# LEDpanelmpsl.net
KiCad netlist of a schematic drawn in EAGLE
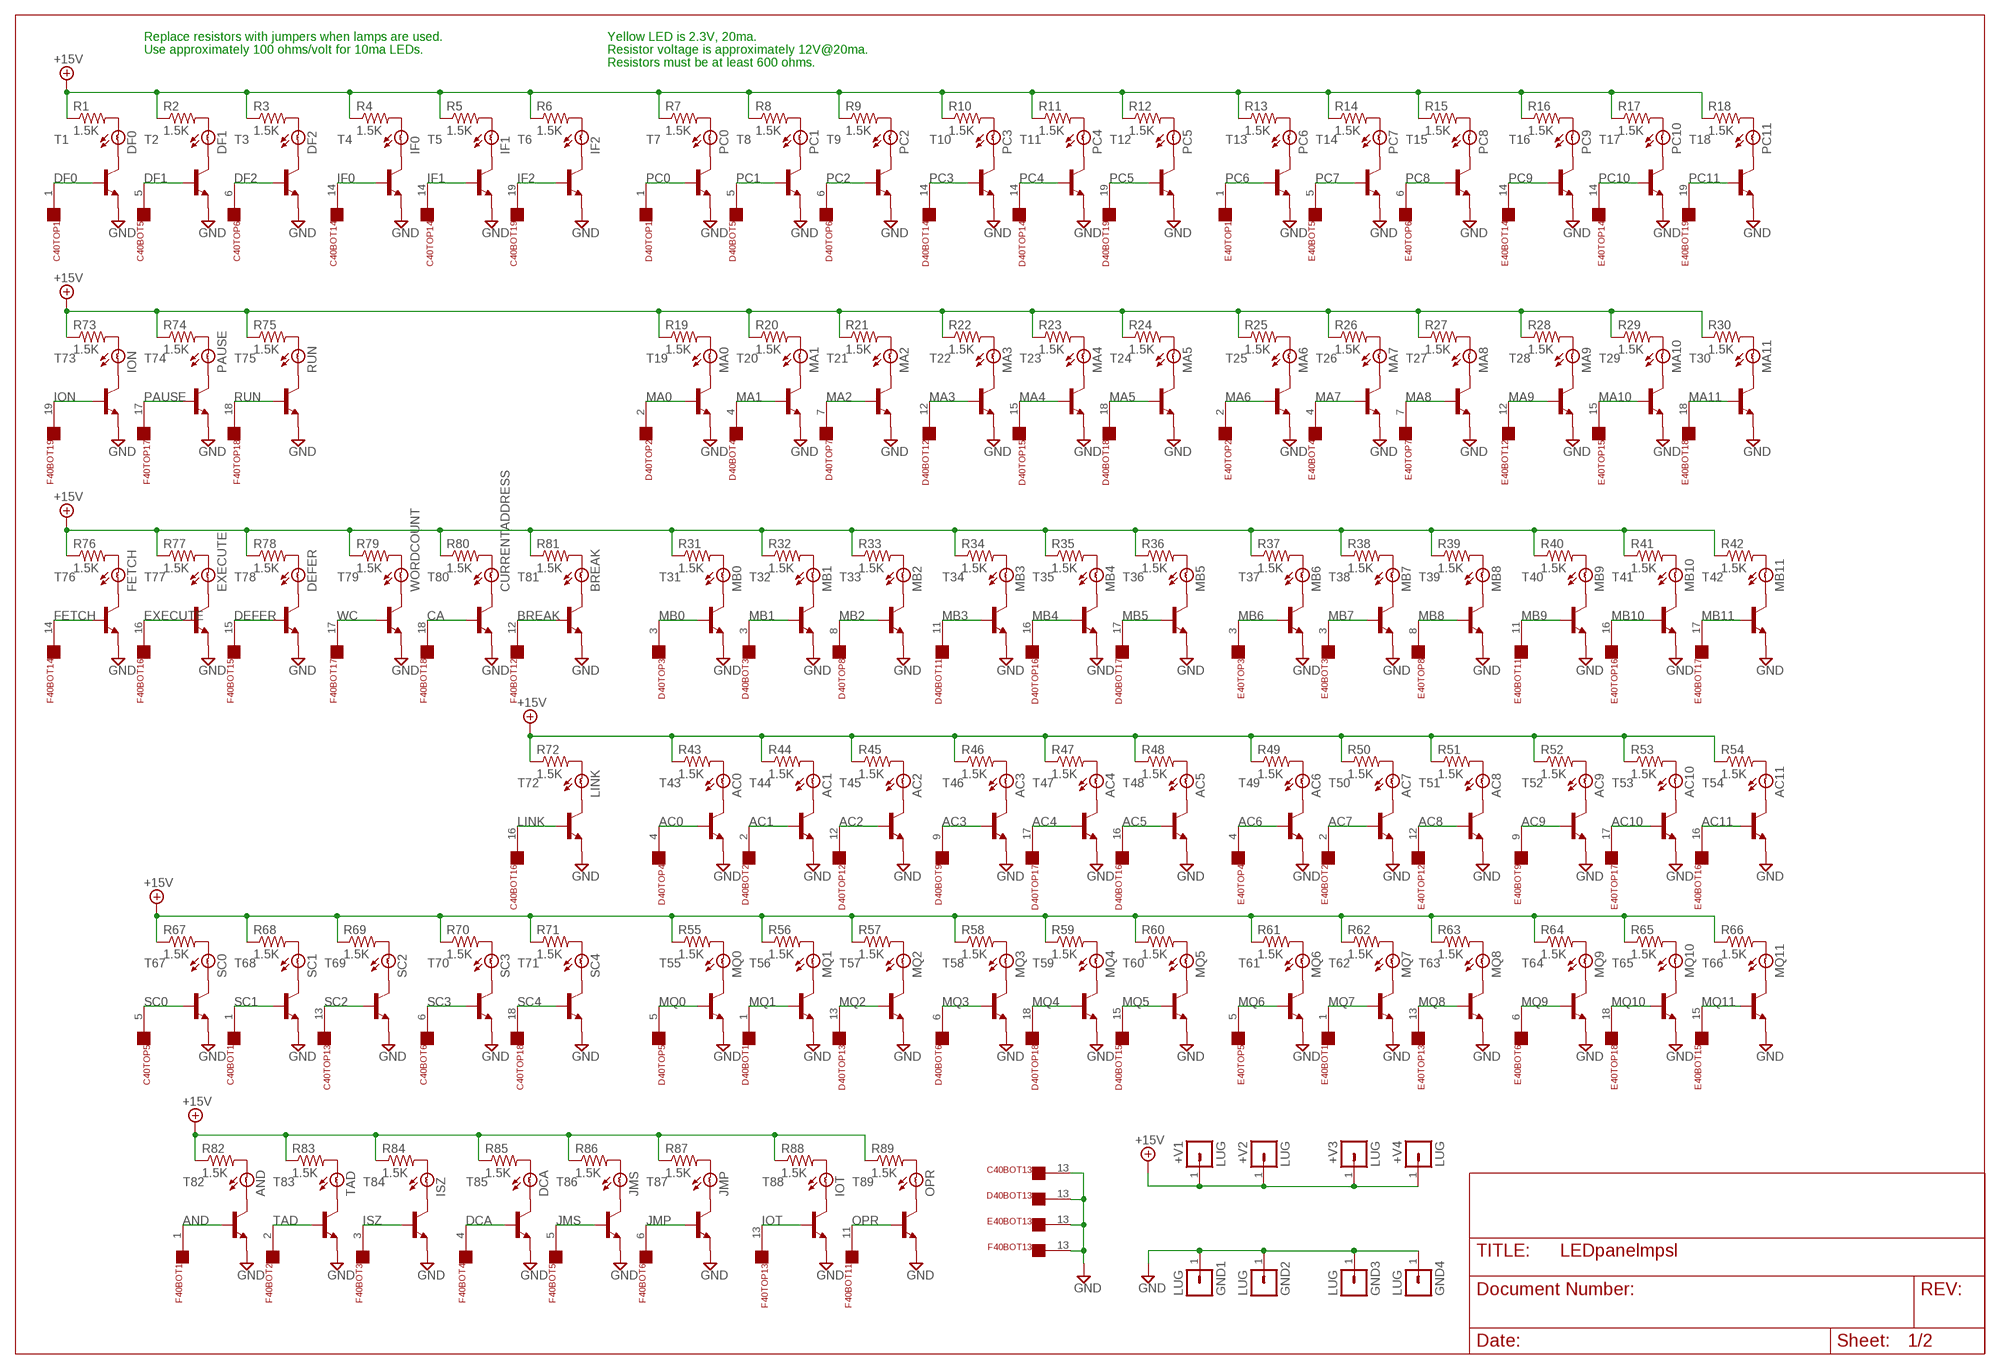
[diagram p0: schematic, sheet 1]
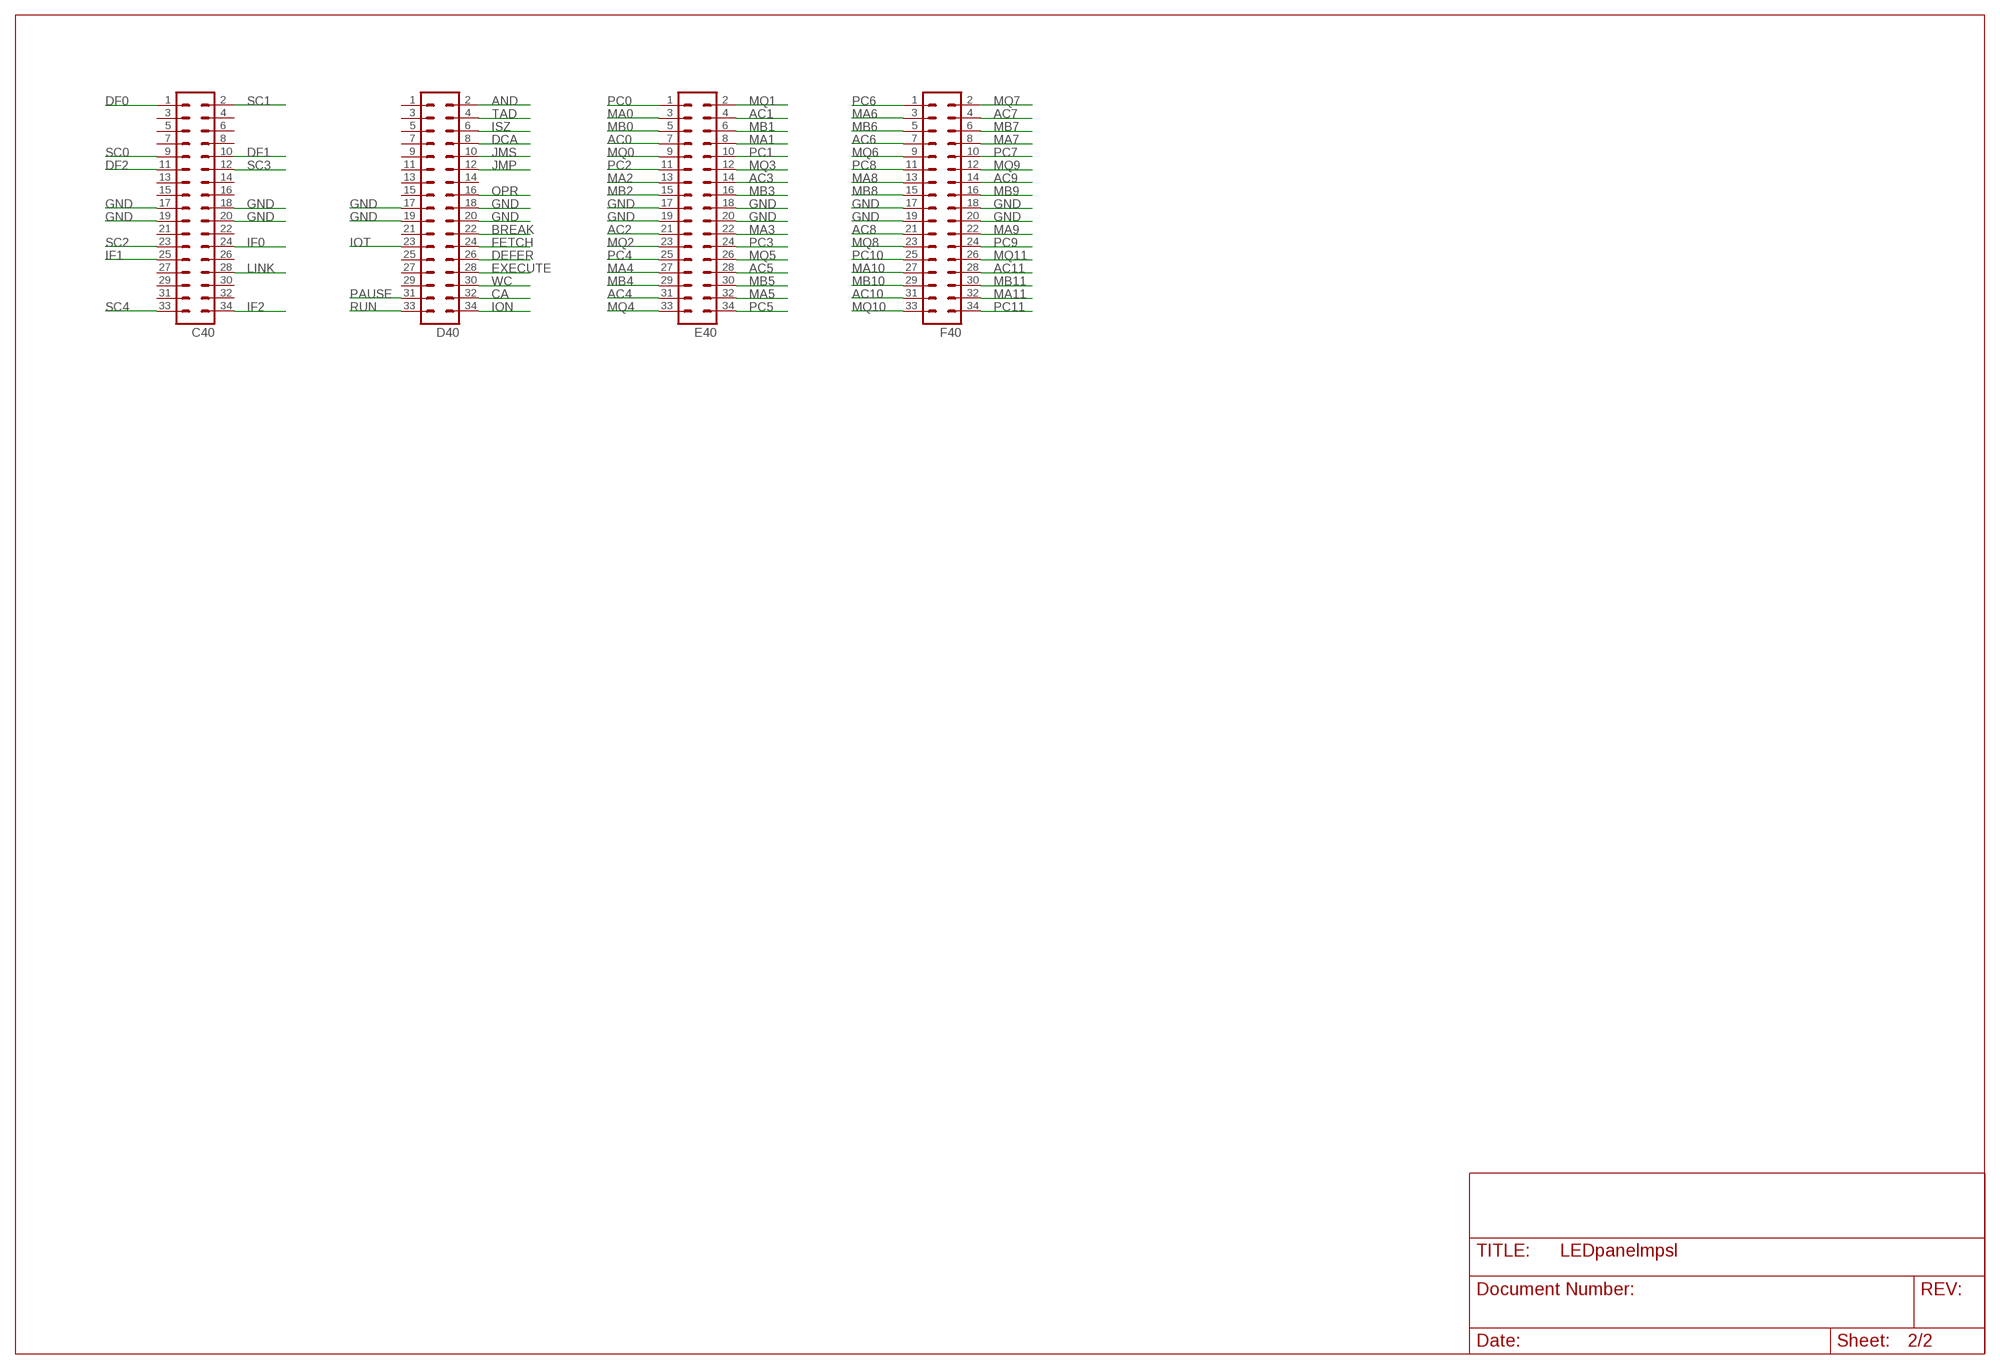
[diagram p1: schematic, sheet 2]

(export (version "E")
  (design (tool "Eeschema 10.0.6"))
  (components
    (comp (ref "+V1")
      (value "LUG")
      (footprint "eagle-import:SPADELUG")
      (libsource (lib "eagle-import") (part "LUG"))
    )
    (comp (ref "+V2")
      (value "LUG")
      (footprint "eagle-import:SPADELUG")
      (libsource (lib "eagle-import") (part "LUG"))
    )
    (comp (ref "+V3")
      (value "LUG")
      (footprint "eagle-import:SPADELUG")
      (libsource (lib "eagle-import") (part "LUG"))
    )
    (comp (ref "+V4")
      (value "LUG")
      (footprint "eagle-import:SPADELUG")
      (libsource (lib "eagle-import") (part "LUG"))
    )
    (comp (ref "AC0")
      (value "BULB")
      (footprint "eagle-import:BULB")
      (libsource (lib "eagle-import") (part "BULB"))
    )
    (comp (ref "AC1")
      (value "BULB")
      (footprint "eagle-import:BULB")
      (libsource (lib "eagle-import") (part "BULB"))
    )
    (comp (ref "AC2")
      (value "BULB")
      (footprint "eagle-import:BULB")
      (libsource (lib "eagle-import") (part "BULB"))
    )
    (comp (ref "AC3")
      (value "BULB")
      (footprint "eagle-import:BULB")
      (libsource (lib "eagle-import") (part "BULB"))
    )
    (comp (ref "AC4")
      (value "BULB")
      (footprint "eagle-import:BULB")
      (libsource (lib "eagle-import") (part "BULB"))
    )
    (comp (ref "AC5")
      (value "BULB")
      (footprint "eagle-import:BULB")
      (libsource (lib "eagle-import") (part "BULB"))
    )
    (comp (ref "AC6")
      (value "BULB")
      (footprint "eagle-import:BULB")
      (libsource (lib "eagle-import") (part "BULB"))
    )
    (comp (ref "AC7")
      (value "BULB")
      (footprint "eagle-import:BULB")
      (libsource (lib "eagle-import") (part "BULB"))
    )
    (comp (ref "AC8")
      (value "BULB")
      (footprint "eagle-import:BULB")
      (libsource (lib "eagle-import") (part "BULB"))
    )
    (comp (ref "AC9")
      (value "BULB")
      (footprint "eagle-import:BULB")
      (libsource (lib "eagle-import") (part "BULB"))
    )
    (comp (ref "AC10")
      (value "BULB")
      (footprint "eagle-import:BULB")
      (libsource (lib "eagle-import") (part "BULB"))
    )
    (comp (ref "AC11")
      (value "BULB")
      (footprint "eagle-import:BULB")
      (libsource (lib "eagle-import") (part "BULB"))
    )
    (comp (ref "AND")
      (value "BULB")
      (footprint "eagle-import:BULB")
      (libsource (lib "eagle-import") (part "BULB"))
    )
    (comp (ref "BREAK")
      (value "BULB")
      (footprint "eagle-import:BULB")
      (libsource (lib "eagle-import") (part "BULB"))
    )
    (comp (ref "C40BOT")
      (value "FLEX19")
      (footprint "eagle-import:FLEX19")
      (libsource (lib "eagle-import") (part "FLEX19"))
    )
    (comp (ref "C40TOP")
      (value "FLEX19")
      (footprint "eagle-import:FLEX19")
      (libsource (lib "eagle-import") (part "FLEX19"))
    )
    (comp (ref "CURRENTADDRESS")
      (value "BULB")
      (footprint "eagle-import:BULB")
      (libsource (lib "eagle-import") (part "BULB"))
    )
    (comp (ref "D40BOT")
      (value "FLEX19")
      (footprint "eagle-import:FLEX19")
      (libsource (lib "eagle-import") (part "FLEX19"))
    )
    (comp (ref "D40TOP")
      (value "FLEX19")
      (footprint "eagle-import:FLEX19")
      (libsource (lib "eagle-import") (part "FLEX19"))
    )
    (comp (ref "DCA")
      (value "BULB")
      (footprint "eagle-import:BULB")
      (libsource (lib "eagle-import") (part "BULB"))
    )
    (comp (ref "DEFER")
      (value "BULB")
      (footprint "eagle-import:BULB")
      (libsource (lib "eagle-import") (part "BULB"))
    )
    (comp (ref "DF0")
      (value "BULB")
      (footprint "eagle-import:BULB")
      (libsource (lib "eagle-import") (part "BULB"))
    )
    (comp (ref "DF1")
      (value "BULB")
      (footprint "eagle-import:BULB")
      (libsource (lib "eagle-import") (part "BULB"))
    )
    (comp (ref "DF2")
      (value "BULB")
      (footprint "eagle-import:BULB")
      (libsource (lib "eagle-import") (part "BULB"))
    )
    (comp (ref "E40BOT")
      (value "FLEX19")
      (footprint "eagle-import:FLEX19")
      (libsource (lib "eagle-import") (part "FLEX19"))
    )
    (comp (ref "E40TOP")
      (value "FLEX19")
      (footprint "eagle-import:FLEX19")
      (libsource (lib "eagle-import") (part "FLEX19"))
    )
    (comp (ref "EXECUTE")
      (value "BULB")
      (footprint "eagle-import:BULB")
      (libsource (lib "eagle-import") (part "BULB"))
    )
    (comp (ref "F40BOT")
      (value "FLEX19")
      (footprint "eagle-import:FLEX19")
      (libsource (lib "eagle-import") (part "FLEX19"))
    )
    (comp (ref "F40TOP")
      (value "FLEX19")
      (footprint "eagle-import:FLEX19")
      (libsource (lib "eagle-import") (part "FLEX19"))
    )
    (comp (ref "FETCH")
      (value "BULB")
      (footprint "eagle-import:BULB")
      (libsource (lib "eagle-import") (part "BULB"))
    )
    (comp (ref "GND1")
      (value "LUG")
      (footprint "eagle-import:SPADELUG")
      (libsource (lib "eagle-import") (part "LUG"))
    )
    (comp (ref "GND2")
      (value "LUG")
      (footprint "eagle-import:SPADELUG")
      (libsource (lib "eagle-import") (part "LUG"))
    )
    (comp (ref "GND3")
      (value "LUG")
      (footprint "eagle-import:SPADELUG")
      (libsource (lib "eagle-import") (part "LUG"))
    )
    (comp (ref "GND4")
      (value "LUG")
      (footprint "eagle-import:SPADELUG")
      (libsource (lib "eagle-import") (part "LUG"))
    )
    (comp (ref "IF0")
      (value "BULB")
      (footprint "eagle-import:BULB")
      (libsource (lib "eagle-import") (part "BULB"))
    )
    (comp (ref "IF1")
      (value "BULB")
      (footprint "eagle-import:BULB")
      (libsource (lib "eagle-import") (part "BULB"))
    )
    (comp (ref "IF2")
      (value "BULB")
      (footprint "eagle-import:BULB")
      (libsource (lib "eagle-import") (part "BULB"))
    )
    (comp (ref "ION")
      (value "BULB")
      (footprint "eagle-import:BULB")
      (libsource (lib "eagle-import") (part "BULB"))
    )
    (comp (ref "IOT")
      (value "BULB")
      (footprint "eagle-import:BULB")
      (libsource (lib "eagle-import") (part "BULB"))
    )
    (comp (ref "ISZ")
      (value "BULB")
      (footprint "eagle-import:BULB")
      (libsource (lib "eagle-import") (part "BULB"))
    )
    (comp (ref "JMP")
      (value "BULB")
      (footprint "eagle-import:BULB")
      (libsource (lib "eagle-import") (part "BULB"))
    )
    (comp (ref "JMS")
      (value "BULB")
      (footprint "eagle-import:BULB")
      (libsource (lib "eagle-import") (part "BULB"))
    )
    (comp (ref "LINK")
      (value "BULB")
      (footprint "eagle-import:BULB")
      (libsource (lib "eagle-import") (part "BULB"))
    )
    (comp (ref "MA0")
      (value "BULB")
      (footprint "eagle-import:BULB")
      (libsource (lib "eagle-import") (part "BULB"))
    )
    (comp (ref "MA1")
      (value "BULB")
      (footprint "eagle-import:BULB")
      (libsource (lib "eagle-import") (part "BULB"))
    )
    (comp (ref "MA2")
      (value "BULB")
      (footprint "eagle-import:BULB")
      (libsource (lib "eagle-import") (part "BULB"))
    )
    (comp (ref "MA3")
      (value "BULB")
      (footprint "eagle-import:BULB")
      (libsource (lib "eagle-import") (part "BULB"))
    )
    (comp (ref "MA4")
      (value "BULB")
      (footprint "eagle-import:BULB")
      (libsource (lib "eagle-import") (part "BULB"))
    )
    (comp (ref "MA5")
      (value "BULB")
      (footprint "eagle-import:BULB")
      (libsource (lib "eagle-import") (part "BULB"))
    )
    (comp (ref "MA6")
      (value "BULB")
      (footprint "eagle-import:BULB")
      (libsource (lib "eagle-import") (part "BULB"))
    )
    (comp (ref "MA7")
      (value "BULB")
      (footprint "eagle-import:BULB")
      (libsource (lib "eagle-import") (part "BULB"))
    )
    (comp (ref "MA8")
      (value "BULB")
      (footprint "eagle-import:BULB")
      (libsource (lib "eagle-import") (part "BULB"))
    )
    (comp (ref "MA9")
      (value "BULB")
      (footprint "eagle-import:BULB")
      (libsource (lib "eagle-import") (part "BULB"))
    )
    (comp (ref "MA10")
      (value "BULB")
      (footprint "eagle-import:BULB")
      (libsource (lib "eagle-import") (part "BULB"))
    )
    (comp (ref "MA11")
      (value "BULB")
      (footprint "eagle-import:BULB")
      (libsource (lib "eagle-import") (part "BULB"))
    )
    (comp (ref "MB0")
      (value "BULB")
      (footprint "eagle-import:BULB")
      (libsource (lib "eagle-import") (part "BULB"))
    )
    (comp (ref "MB1")
      (value "BULB")
      (footprint "eagle-import:BULB")
      (libsource (lib "eagle-import") (part "BULB"))
    )
    (comp (ref "MB2")
      (value "BULB")
      (footprint "eagle-import:BULB")
      (libsource (lib "eagle-import") (part "BULB"))
    )
    (comp (ref "MB3")
      (value "BULB")
      (footprint "eagle-import:BULB")
      (libsource (lib "eagle-import") (part "BULB"))
    )
    (comp (ref "MB4")
      (value "BULB")
      (footprint "eagle-import:BULB")
      (libsource (lib "eagle-import") (part "BULB"))
    )
    (comp (ref "MB5")
      (value "BULB")
      (footprint "eagle-import:BULB")
      (libsource (lib "eagle-import") (part "BULB"))
    )
    (comp (ref "MB6")
      (value "BULB")
      (footprint "eagle-import:BULB")
      (libsource (lib "eagle-import") (part "BULB"))
    )
    (comp (ref "MB7")
      (value "BULB")
      (footprint "eagle-import:BULB")
      (libsource (lib "eagle-import") (part "BULB"))
    )
    (comp (ref "MB8")
      (value "BULB")
      (footprint "eagle-import:BULB")
      (libsource (lib "eagle-import") (part "BULB"))
    )
    (comp (ref "MB9")
      (value "BULB")
      (footprint "eagle-import:BULB")
      (libsource (lib "eagle-import") (part "BULB"))
    )
    (comp (ref "MB10")
      (value "BULB")
      (footprint "eagle-import:BULB")
      (libsource (lib "eagle-import") (part "BULB"))
    )
    (comp (ref "MB11")
      (value "BULB")
      (footprint "eagle-import:BULB")
      (libsource (lib "eagle-import") (part "BULB"))
    )
    (comp (ref "MQ0")
      (value "BULB")
      (footprint "eagle-import:BULB")
      (libsource (lib "eagle-import") (part "BULB"))
    )
    (comp (ref "MQ1")
      (value "BULB")
      (footprint "eagle-import:BULB")
      (libsource (lib "eagle-import") (part "BULB"))
    )
    (comp (ref "MQ2")
      (value "BULB")
      (footprint "eagle-import:BULB")
      (libsource (lib "eagle-import") (part "BULB"))
    )
    (comp (ref "MQ3")
      (value "BULB")
      (footprint "eagle-import:BULB")
      (libsource (lib "eagle-import") (part "BULB"))
    )
    (comp (ref "MQ4")
      (value "BULB")
      (footprint "eagle-import:BULB")
      (libsource (lib "eagle-import") (part "BULB"))
    )
    (comp (ref "MQ5")
      (value "BULB")
      (footprint "eagle-import:BULB")
      (libsource (lib "eagle-import") (part "BULB"))
    )
    (comp (ref "MQ6")
      (value "BULB")
      (footprint "eagle-import:BULB")
      (libsource (lib "eagle-import") (part "BULB"))
    )
    (comp (ref "MQ7")
      (value "BULB")
      (footprint "eagle-import:BULB")
      (libsource (lib "eagle-import") (part "BULB"))
    )
    (comp (ref "MQ8")
      (value "BULB")
      (footprint "eagle-import:BULB")
      (libsource (lib "eagle-import") (part "BULB"))
    )
    (comp (ref "MQ9")
      (value "BULB")
      (footprint "eagle-import:BULB")
      (libsource (lib "eagle-import") (part "BULB"))
    )
    (comp (ref "MQ10")
      (value "BULB")
      (footprint "eagle-import:BULB")
      (libsource (lib "eagle-import") (part "BULB"))
    )
    (comp (ref "MQ11")
      (value "BULB")
      (footprint "eagle-import:BULB")
      (libsource (lib "eagle-import") (part "BULB"))
    )
    (comp (ref "OPR")
      (value "BULB")
      (footprint "eagle-import:BULB")
      (libsource (lib "eagle-import") (part "BULB"))
    )
    (comp (ref "PAUSE")
      (value "BULB")
      (footprint "eagle-import:BULB")
      (libsource (lib "eagle-import") (part "BULB"))
    )
    (comp (ref "PC0")
      (value "BULB")
      (footprint "eagle-import:BULB")
      (libsource (lib "eagle-import") (part "BULB"))
    )
    (comp (ref "PC1")
      (value "BULB")
      (footprint "eagle-import:BULB")
      (libsource (lib "eagle-import") (part "BULB"))
    )
    (comp (ref "PC2")
      (value "BULB")
      (footprint "eagle-import:BULB")
      (libsource (lib "eagle-import") (part "BULB"))
    )
    (comp (ref "PC3")
      (value "BULB")
      (footprint "eagle-import:BULB")
      (libsource (lib "eagle-import") (part "BULB"))
    )
    (comp (ref "PC4")
      (value "BULB")
      (footprint "eagle-import:BULB")
      (libsource (lib "eagle-import") (part "BULB"))
    )
    (comp (ref "PC5")
      (value "BULB")
      (footprint "eagle-import:BULB")
      (libsource (lib "eagle-import") (part "BULB"))
    )
    (comp (ref "PC6")
      (value "BULB")
      (footprint "eagle-import:BULB")
      (libsource (lib "eagle-import") (part "BULB"))
    )
    (comp (ref "PC7")
      (value "BULB")
      (footprint "eagle-import:BULB")
      (libsource (lib "eagle-import") (part "BULB"))
    )
    (comp (ref "PC8")
      (value "BULB")
      (footprint "eagle-import:BULB")
      (libsource (lib "eagle-import") (part "BULB"))
    )
    (comp (ref "PC9")
      (value "BULB")
      (footprint "eagle-import:BULB")
      (libsource (lib "eagle-import") (part "BULB"))
    )
    (comp (ref "PC10")
      (value "BULB")
      (footprint "eagle-import:BULB")
      (libsource (lib "eagle-import") (part "BULB"))
    )
    (comp (ref "PC11")
      (value "BULB")
      (footprint "eagle-import:BULB")
      (libsource (lib "eagle-import") (part "BULB"))
    )
    (comp (ref "R1")
      (value "1.5K")
      (footprint "eagle-import:0207_10")
      (libsource (lib "eagle-import") (part "R-US_0207/10"))
    )
    (comp (ref "R2")
      (value "1.5K")
      (footprint "eagle-import:0207_10")
      (libsource (lib "eagle-import") (part "R-US_0207/10"))
    )
    (comp (ref "R3")
      (value "1.5K")
      (footprint "eagle-import:0207_10")
      (libsource (lib "eagle-import") (part "R-US_0207/10"))
    )
    (comp (ref "R4")
      (value "1.5K")
      (footprint "eagle-import:0207_10")
      (libsource (lib "eagle-import") (part "R-US_0207/10"))
    )
    (comp (ref "R5")
      (value "1.5K")
      (footprint "eagle-import:0207_10")
      (libsource (lib "eagle-import") (part "R-US_0207/10"))
    )
    (comp (ref "R6")
      (value "1.5K")
      (footprint "eagle-import:0207_10")
      (libsource (lib "eagle-import") (part "R-US_0207/10"))
    )
    (comp (ref "R7")
      (value "1.5K")
      (footprint "eagle-import:0207_10")
      (libsource (lib "eagle-import") (part "R-US_0207/10"))
    )
    (comp (ref "R8")
      (value "1.5K")
      (footprint "eagle-import:0207_10")
      (libsource (lib "eagle-import") (part "R-US_0207/10"))
    )
    (comp (ref "R9")
      (value "1.5K")
      (footprint "eagle-import:0207_10")
      (libsource (lib "eagle-import") (part "R-US_0207/10"))
    )
    (comp (ref "R10")
      (value "1.5K")
      (footprint "eagle-import:0207_10")
      (libsource (lib "eagle-import") (part "R-US_0207/10"))
    )
    (comp (ref "R11")
      (value "1.5K")
      (footprint "eagle-import:0207_10")
      (libsource (lib "eagle-import") (part "R-US_0207/10"))
    )
    (comp (ref "R12")
      (value "1.5K")
      (footprint "eagle-import:0207_10")
      (libsource (lib "eagle-import") (part "R-US_0207/10"))
    )
    (comp (ref "R13")
      (value "1.5K")
      (footprint "eagle-import:0207_10")
      (libsource (lib "eagle-import") (part "R-US_0207/10"))
    )
    (comp (ref "R14")
      (value "1.5K")
      (footprint "eagle-import:0207_10")
      (libsource (lib "eagle-import") (part "R-US_0207/10"))
    )
    (comp (ref "R15")
      (value "1.5K")
      (footprint "eagle-import:0207_10")
      (libsource (lib "eagle-import") (part "R-US_0207/10"))
    )
    (comp (ref "R16")
      (value "1.5K")
      (footprint "eagle-import:0207_10")
      (libsource (lib "eagle-import") (part "R-US_0207/10"))
    )
    (comp (ref "R17")
      (value "1.5K")
      (footprint "eagle-import:0207_10")
      (libsource (lib "eagle-import") (part "R-US_0207/10"))
    )
    (comp (ref "R18")
      (value "1.5K")
      (footprint "eagle-import:0207_10")
      (libsource (lib "eagle-import") (part "R-US_0207/10"))
    )
    (comp (ref "R19")
      (value "1.5K")
      (footprint "eagle-import:0207_10")
      (libsource (lib "eagle-import") (part "R-US_0207/10"))
    )
    (comp (ref "R20")
      (value "1.5K")
      (footprint "eagle-import:0207_10")
      (libsource (lib "eagle-import") (part "R-US_0207/10"))
    )
    (comp (ref "R21")
      (value "1.5K")
      (footprint "eagle-import:0207_10")
      (libsource (lib "eagle-import") (part "R-US_0207/10"))
    )
    (comp (ref "R22")
      (value "1.5K")
      (footprint "eagle-import:0207_10")
      (libsource (lib "eagle-import") (part "R-US_0207/10"))
    )
    (comp (ref "R23")
      (value "1.5K")
      (footprint "eagle-import:0207_10")
      (libsource (lib "eagle-import") (part "R-US_0207/10"))
    )
    (comp (ref "R24")
      (value "1.5K")
      (footprint "eagle-import:0207_10")
      (libsource (lib "eagle-import") (part "R-US_0207/10"))
    )
    (comp (ref "R25")
      (value "1.5K")
      (footprint "eagle-import:0207_10")
      (libsource (lib "eagle-import") (part "R-US_0207/10"))
    )
    (comp (ref "R26")
      (value "1.5K")
      (footprint "eagle-import:0207_10")
      (libsource (lib "eagle-import") (part "R-US_0207/10"))
    )
    (comp (ref "R27")
      (value "1.5K")
      (footprint "eagle-import:0207_10")
      (libsource (lib "eagle-import") (part "R-US_0207/10"))
    )
    (comp (ref "R28")
      (value "1.5K")
      (footprint "eagle-import:0207_10")
      (libsource (lib "eagle-import") (part "R-US_0207/10"))
    )
    (comp (ref "R29")
      (value "1.5K")
      (footprint "eagle-import:0207_10")
      (libsource (lib "eagle-import") (part "R-US_0207/10"))
    )
    (comp (ref "R30")
      (value "1.5K")
      (footprint "eagle-import:0207_10")
      (libsource (lib "eagle-import") (part "R-US_0207/10"))
    )
    (comp (ref "R31")
      (value "1.5K")
      (footprint "eagle-import:0207_10")
      (libsource (lib "eagle-import") (part "R-US_0207/10"))
    )
    (comp (ref "R32")
      (value "1.5K")
      (footprint "eagle-import:0207_10")
      (libsource (lib "eagle-import") (part "R-US_0207/10"))
    )
    (comp (ref "R33")
      (value "1.5K")
      (footprint "eagle-import:0207_10")
      (libsource (lib "eagle-import") (part "R-US_0207/10"))
    )
    (comp (ref "R34")
      (value "1.5K")
      (footprint "eagle-import:0207_10")
      (libsource (lib "eagle-import") (part "R-US_0207/10"))
    )
    (comp (ref "R35")
      (value "1.5K")
      (footprint "eagle-import:0207_10")
      (libsource (lib "eagle-import") (part "R-US_0207/10"))
    )
    (comp (ref "R36")
      (value "1.5K")
      (footprint "eagle-import:0207_10")
      (libsource (lib "eagle-import") (part "R-US_0207/10"))
    )
    (comp (ref "R37")
      (value "1.5K")
      (footprint "eagle-import:0207_10")
      (libsource (lib "eagle-import") (part "R-US_0207/10"))
    )
    (comp (ref "R38")
      (value "1.5K")
      (footprint "eagle-import:0207_10")
      (libsource (lib "eagle-import") (part "R-US_0207/10"))
    )
    (comp (ref "R39")
      (value "1.5K")
      (footprint "eagle-import:0207_10")
      (libsource (lib "eagle-import") (part "R-US_0207/10"))
    )
    (comp (ref "R40")
      (value "1.5K")
      (footprint "eagle-import:0207_10")
      (libsource (lib "eagle-import") (part "R-US_0207/10"))
    )
    (comp (ref "R41")
      (value "1.5K")
      (footprint "eagle-import:0207_10")
      (libsource (lib "eagle-import") (part "R-US_0207/10"))
    )
    (comp (ref "R42")
      (value "1.5K")
      (footprint "eagle-import:0207_10")
      (libsource (lib "eagle-import") (part "R-US_0207/10"))
    )
    (comp (ref "R43")
      (value "1.5K")
      (footprint "eagle-import:0207_10")
      (libsource (lib "eagle-import") (part "R-US_0207/10"))
    )
    (comp (ref "R44")
      (value "1.5K")
      (footprint "eagle-import:0207_10")
      (libsource (lib "eagle-import") (part "R-US_0207/10"))
    )
    (comp (ref "R45")
      (value "1.5K")
      (footprint "eagle-import:0207_10")
      (libsource (lib "eagle-import") (part "R-US_0207/10"))
    )
    (comp (ref "R46")
      (value "1.5K")
      (footprint "eagle-import:0207_10")
      (libsource (lib "eagle-import") (part "R-US_0207/10"))
    )
    (comp (ref "R47")
      (value "1.5K")
      (footprint "eagle-import:0207_10")
      (libsource (lib "eagle-import") (part "R-US_0207/10"))
    )
    (comp (ref "R48")
      (value "1.5K")
      (footprint "eagle-import:0207_10")
      (libsource (lib "eagle-import") (part "R-US_0207/10"))
    )
    (comp (ref "R49")
      (value "1.5K")
      (footprint "eagle-import:0207_10")
      (libsource (lib "eagle-import") (part "R-US_0207/10"))
    )
    (comp (ref "R50")
      (value "1.5K")
      (footprint "eagle-import:0207_10")
      (libsource (lib "eagle-import") (part "R-US_0207/10"))
    )
    (comp (ref "R51")
      (value "1.5K")
      (footprint "eagle-import:0207_10")
      (libsource (lib "eagle-import") (part "R-US_0207/10"))
    )
    (comp (ref "R52")
      (value "1.5K")
      (footprint "eagle-import:0207_10")
      (libsource (lib "eagle-import") (part "R-US_0207/10"))
    )
    (comp (ref "R53")
      (value "1.5K")
      (footprint "eagle-import:0207_10")
      (libsource (lib "eagle-import") (part "R-US_0207/10"))
    )
    (comp (ref "R54")
      (value "1.5K")
      (footprint "eagle-import:0207_10")
      (libsource (lib "eagle-import") (part "R-US_0207/10"))
    )
    (comp (ref "R55")
      (value "1.5K")
      (footprint "eagle-import:0207_10")
      (libsource (lib "eagle-import") (part "R-US_0207/10"))
    )
    (comp (ref "R56")
      (value "1.5K")
      (footprint "eagle-import:0207_10")
      (libsource (lib "eagle-import") (part "R-US_0207/10"))
    )
    (comp (ref "R57")
      (value "1.5K")
      (footprint "eagle-import:0207_10")
      (libsource (lib "eagle-import") (part "R-US_0207/10"))
    )
    (comp (ref "R58")
      (value "1.5K")
      (footprint "eagle-import:0207_10")
      (libsource (lib "eagle-import") (part "R-US_0207/10"))
    )
    (comp (ref "R59")
      (value "1.5K")
      (footprint "eagle-import:0207_10")
      (libsource (lib "eagle-import") (part "R-US_0207/10"))
    )
    (comp (ref "R60")
      (value "1.5K")
      (footprint "eagle-import:0207_10")
      (libsource (lib "eagle-import") (part "R-US_0207/10"))
    )
    (comp (ref "R61")
      (value "1.5K")
      (footprint "eagle-import:0207_10")
      (libsource (lib "eagle-import") (part "R-US_0207/10"))
    )
    (comp (ref "R62")
      (value "1.5K")
      (footprint "eagle-import:0207_10")
      (libsource (lib "eagle-import") (part "R-US_0207/10"))
    )
    (comp (ref "R63")
      (value "1.5K")
      (footprint "eagle-import:0207_10")
      (libsource (lib "eagle-import") (part "R-US_0207/10"))
    )
    (comp (ref "R64")
      (value "1.5K")
      (footprint "eagle-import:0207_10")
      (libsource (lib "eagle-import") (part "R-US_0207/10"))
    )
    (comp (ref "R65")
      (value "1.5K")
      (footprint "eagle-import:0207_10")
      (libsource (lib "eagle-import") (part "R-US_0207/10"))
    )
    (comp (ref "R66")
      (value "1.5K")
      (footprint "eagle-import:0207_10")
      (libsource (lib "eagle-import") (part "R-US_0207/10"))
    )
    (comp (ref "R67")
      (value "1.5K")
      (footprint "eagle-import:0207_10")
      (libsource (lib "eagle-import") (part "R-US_0207/10"))
    )
    (comp (ref "R68")
      (value "1.5K")
      (footprint "eagle-import:0207_10")
      (libsource (lib "eagle-import") (part "R-US_0207/10"))
    )
    (comp (ref "R69")
      (value "1.5K")
      (footprint "eagle-import:0207_10")
      (libsource (lib "eagle-import") (part "R-US_0207/10"))
    )
    (comp (ref "R70")
      (value "1.5K")
      (footprint "eagle-import:0207_10")
      (libsource (lib "eagle-import") (part "R-US_0207/10"))
    )
    (comp (ref "R71")
      (value "1.5K")
      (footprint "eagle-import:0207_10")
      (libsource (lib "eagle-import") (part "R-US_0207/10"))
    )
    (comp (ref "R72")
      (value "1.5K")
      (footprint "eagle-import:0207_10")
      (libsource (lib "eagle-import") (part "R-US_0207/10"))
    )
    (comp (ref "R73")
      (value "1.5K")
      (footprint "eagle-import:0207_10")
      (libsource (lib "eagle-import") (part "R-US_0207/10"))
    )
    (comp (ref "R74")
      (value "1.5K")
      (footprint "eagle-import:0207_10")
      (libsource (lib "eagle-import") (part "R-US_0207/10"))
    )
    (comp (ref "R75")
      (value "1.5K")
      (footprint "eagle-import:0207_10")
      (libsource (lib "eagle-import") (part "R-US_0207/10"))
    )
    (comp (ref "R76")
      (value "1.5K")
      (footprint "eagle-import:0207_10")
      (libsource (lib "eagle-import") (part "R-US_0207/10"))
    )
    (comp (ref "R77")
      (value "1.5K")
      (footprint "eagle-import:0207_10")
      (libsource (lib "eagle-import") (part "R-US_0207/10"))
    )
    (comp (ref "R78")
      (value "1.5K")
      (footprint "eagle-import:0207_10")
      (libsource (lib "eagle-import") (part "R-US_0207/10"))
    )
    (comp (ref "R79")
      (value "1.5K")
      (footprint "eagle-import:0207_10")
      (libsource (lib "eagle-import") (part "R-US_0207/10"))
    )
    (comp (ref "R80")
      (value "1.5K")
      (footprint "eagle-import:0207_10")
      (libsource (lib "eagle-import") (part "R-US_0207/10"))
    )
    (comp (ref "R81")
      (value "1.5K")
      (footprint "eagle-import:0207_10")
      (libsource (lib "eagle-import") (part "R-US_0207/10"))
    )
    (comp (ref "R82")
      (value "1.5K")
      (footprint "eagle-import:0207_10")
      (libsource (lib "eagle-import") (part "R-US_0207/10"))
    )
    (comp (ref "R83")
      (value "1.5K")
      (footprint "eagle-import:0207_10")
      (libsource (lib "eagle-import") (part "R-US_0207/10"))
    )
    (comp (ref "R84")
      (value "1.5K")
      (footprint "eagle-import:0207_10")
      (libsource (lib "eagle-import") (part "R-US_0207/10"))
    )
    (comp (ref "R85")
      (value "1.5K")
      (footprint "eagle-import:0207_10")
      (libsource (lib "eagle-import") (part "R-US_0207/10"))
    )
    (comp (ref "R86")
      (value "1.5K")
      (footprint "eagle-import:0207_10")
      (libsource (lib "eagle-import") (part "R-US_0207/10"))
    )
    (comp (ref "R87")
      (value "1.5K")
      (footprint "eagle-import:0207_10")
      (libsource (lib "eagle-import") (part "R-US_0207/10"))
    )
    (comp (ref "R88")
      (value "1.5K")
      (footprint "eagle-import:0207_10")
      (libsource (lib "eagle-import") (part "R-US_0207/10"))
    )
    (comp (ref "R89")
      (value "1.5K")
      (footprint "eagle-import:0207_10")
      (libsource (lib "eagle-import") (part "R-US_0207/10"))
    )
    (comp (ref "RUN")
      (value "BULB")
      (footprint "eagle-import:BULB")
      (libsource (lib "eagle-import") (part "BULB"))
    )
    (comp (ref "SC0")
      (value "BULB")
      (footprint "eagle-import:BULB")
      (libsource (lib "eagle-import") (part "BULB"))
    )
    (comp (ref "SC1")
      (value "BULB")
      (footprint "eagle-import:BULB")
      (libsource (lib "eagle-import") (part "BULB"))
    )
    (comp (ref "SC2")
      (value "BULB")
      (footprint "eagle-import:BULB")
      (libsource (lib "eagle-import") (part "BULB"))
    )
    (comp (ref "SC3")
      (value "BULB")
      (footprint "eagle-import:BULB")
      (libsource (lib "eagle-import") (part "BULB"))
    )
    (comp (ref "SC4")
      (value "BULB")
      (footprint "eagle-import:BULB")
      (libsource (lib "eagle-import") (part "BULB"))
    )
    (comp (ref "T1")
      (value "MPS2222A-NPN-TO92-CBE")
      (footprint "eagle-import:TO92-CBE")
      (libsource (lib "eagle-import") (part "-NPN-TO92-CBEMPS2222A"))
    )
    (comp (ref "T2")
      (value "MPS2222A-NPN-TO92-CBE")
      (footprint "eagle-import:TO92-CBE")
      (libsource (lib "eagle-import") (part "-NPN-TO92-CBEMPS2222A"))
    )
    (comp (ref "T3")
      (value "MPS2222A-NPN-TO92-CBE")
      (footprint "eagle-import:TO92-CBE")
      (libsource (lib "eagle-import") (part "-NPN-TO92-CBEMPS2222A"))
    )
    (comp (ref "T4")
      (value "MPS2222A-NPN-TO92-CBE")
      (footprint "eagle-import:TO92-CBE")
      (libsource (lib "eagle-import") (part "-NPN-TO92-CBEMPS2222A"))
    )
    (comp (ref "T5")
      (value "MPS2222A-NPN-TO92-CBE")
      (footprint "eagle-import:TO92-CBE")
      (libsource (lib "eagle-import") (part "-NPN-TO92-CBEMPS2222A"))
    )
    (comp (ref "T6")
      (value "MPS2222A-NPN-TO92-CBE")
      (footprint "eagle-import:TO92-CBE")
      (libsource (lib "eagle-import") (part "-NPN-TO92-CBEMPS2222A"))
    )
    (comp (ref "T7")
      (value "MPS2222A-NPN-TO92-CBE")
      (footprint "eagle-import:TO92-CBE")
      (libsource (lib "eagle-import") (part "-NPN-TO92-CBEMPS2222A"))
    )
    (comp (ref "T8")
      (value "MPS2222A-NPN-TO92-CBE")
      (footprint "eagle-import:TO92-CBE")
      (libsource (lib "eagle-import") (part "-NPN-TO92-CBEMPS2222A"))
    )
    (comp (ref "T9")
      (value "MPS2222A-NPN-TO92-CBE")
      (footprint "eagle-import:TO92-CBE")
      (libsource (lib "eagle-import") (part "-NPN-TO92-CBEMPS2222A"))
    )
    (comp (ref "T10")
      (value "MPS2222A-NPN-TO92-CBE")
      (footprint "eagle-import:TO92-CBE")
      (libsource (lib "eagle-import") (part "-NPN-TO92-CBEMPS2222A"))
    )
    (comp (ref "T11")
      (value "MPS2222A-NPN-TO92-CBE")
      (footprint "eagle-import:TO92-CBE")
      (libsource (lib "eagle-import") (part "-NPN-TO92-CBEMPS2222A"))
    )
    (comp (ref "T12")
      (value "MPS2222A-NPN-TO92-CBE")
      (footprint "eagle-import:TO92-CBE")
      (libsource (lib "eagle-import") (part "-NPN-TO92-CBEMPS2222A"))
    )
    (comp (ref "T13")
      (value "MPS2222A-NPN-TO92-CBE")
      (footprint "eagle-import:TO92-CBE")
      (libsource (lib "eagle-import") (part "-NPN-TO92-CBEMPS2222A"))
    )
    (comp (ref "T14")
      (value "MPS2222A-NPN-TO92-CBE")
      (footprint "eagle-import:TO92-CBE")
      (libsource (lib "eagle-import") (part "-NPN-TO92-CBEMPS2222A"))
    )
    (comp (ref "T15")
      (value "MPS2222A-NPN-TO92-CBE")
      (footprint "eagle-import:TO92-CBE")
      (libsource (lib "eagle-import") (part "-NPN-TO92-CBEMPS2222A"))
    )
    (comp (ref "T16")
      (value "MPS2222A-NPN-TO92-CBE")
      (footprint "eagle-import:TO92-CBE")
      (libsource (lib "eagle-import") (part "-NPN-TO92-CBEMPS2222A"))
    )
    (comp (ref "T17")
      (value "MPS2222A-NPN-TO92-CBE")
      (footprint "eagle-import:TO92-CBE")
      (libsource (lib "eagle-import") (part "-NPN-TO92-CBEMPS2222A"))
    )
    (comp (ref "T18")
      (value "MPS2222A-NPN-TO92-CBE")
      (footprint "eagle-import:TO92-CBE")
      (libsource (lib "eagle-import") (part "-NPN-TO92-CBEMPS2222A"))
    )
    (comp (ref "T19")
      (value "MPS2222A-NPN-TO92-CBE")
      (footprint "eagle-import:TO92-CBE")
      (libsource (lib "eagle-import") (part "-NPN-TO92-CBEMPS2222A"))
    )
    (comp (ref "T20")
      (value "MPS2222A-NPN-TO92-CBE")
      (footprint "eagle-import:TO92-CBE")
      (libsource (lib "eagle-import") (part "-NPN-TO92-CBEMPS2222A"))
    )
    (comp (ref "T21")
      (value "MPS2222A-NPN-TO92-CBE")
      (footprint "eagle-import:TO92-CBE")
      (libsource (lib "eagle-import") (part "-NPN-TO92-CBEMPS2222A"))
    )
    (comp (ref "T22")
      (value "MPS2222A-NPN-TO92-CBE")
      (footprint "eagle-import:TO92-CBE")
      (libsource (lib "eagle-import") (part "-NPN-TO92-CBEMPS2222A"))
    )
    (comp (ref "T23")
      (value "MPS2222A-NPN-TO92-CBE")
      (footprint "eagle-import:TO92-CBE")
      (libsource (lib "eagle-import") (part "-NPN-TO92-CBEMPS2222A"))
    )
    (comp (ref "T24")
      (value "MPS2222A-NPN-TO92-CBE")
      (footprint "eagle-import:TO92-CBE")
      (libsource (lib "eagle-import") (part "-NPN-TO92-CBEMPS2222A"))
    )
    (comp (ref "T25")
      (value "MPS2222A-NPN-TO92-CBE")
      (footprint "eagle-import:TO92-CBE")
      (libsource (lib "eagle-import") (part "-NPN-TO92-CBEMPS2222A"))
    )
    (comp (ref "T26")
      (value "MPS2222A-NPN-TO92-CBE")
      (footprint "eagle-import:TO92-CBE")
      (libsource (lib "eagle-import") (part "-NPN-TO92-CBEMPS2222A"))
    )
    (comp (ref "T27")
      (value "MPS2222A-NPN-TO92-CBE")
      (footprint "eagle-import:TO92-CBE")
      (libsource (lib "eagle-import") (part "-NPN-TO92-CBEMPS2222A"))
    )
    (comp (ref "T28")
      (value "MPS2222A-NPN-TO92-CBE")
      (footprint "eagle-import:TO92-CBE")
      (libsource (lib "eagle-import") (part "-NPN-TO92-CBEMPS2222A"))
    )
    (comp (ref "T29")
      (value "MPS2222A-NPN-TO92-CBE")
      (footprint "eagle-import:TO92-CBE")
      (libsource (lib "eagle-import") (part "-NPN-TO92-CBEMPS2222A"))
    )
    (comp (ref "T30")
      (value "MPS2222A-NPN-TO92-CBE")
      (footprint "eagle-import:TO92-CBE")
      (libsource (lib "eagle-import") (part "-NPN-TO92-CBEMPS2222A"))
    )
    (comp (ref "T31")
      (value "MPS2222A-NPN-TO92-CBE")
      (footprint "eagle-import:TO92-CBE")
      (libsource (lib "eagle-import") (part "-NPN-TO92-CBEMPS2222A"))
    )
    (comp (ref "T32")
      (value "MPS2222A-NPN-TO92-CBE")
      (footprint "eagle-import:TO92-CBE")
      (libsource (lib "eagle-import") (part "-NPN-TO92-CBEMPS2222A"))
    )
    (comp (ref "T33")
      (value "MPS2222A-NPN-TO92-CBE")
      (footprint "eagle-import:TO92-CBE")
      (libsource (lib "eagle-import") (part "-NPN-TO92-CBEMPS2222A"))
    )
    (comp (ref "T34")
      (value "MPS2222A-NPN-TO92-CBE")
      (footprint "eagle-import:TO92-CBE")
      (libsource (lib "eagle-import") (part "-NPN-TO92-CBEMPS2222A"))
    )
    (comp (ref "T35")
      (value "MPS2222A-NPN-TO92-CBE")
      (footprint "eagle-import:TO92-CBE")
      (libsource (lib "eagle-import") (part "-NPN-TO92-CBEMPS2222A"))
    )
    (comp (ref "T36")
      (value "MPS2222A-NPN-TO92-CBE")
      (footprint "eagle-import:TO92-CBE")
      (libsource (lib "eagle-import") (part "-NPN-TO92-CBEMPS2222A"))
    )
    (comp (ref "T37")
      (value "MPS2222A-NPN-TO92-CBE")
      (footprint "eagle-import:TO92-CBE")
      (libsource (lib "eagle-import") (part "-NPN-TO92-CBEMPS2222A"))
    )
    (comp (ref "T38")
      (value "MPS2222A-NPN-TO92-CBE")
      (footprint "eagle-import:TO92-CBE")
      (libsource (lib "eagle-import") (part "-NPN-TO92-CBEMPS2222A"))
    )
    (comp (ref "T39")
      (value "MPS2222A-NPN-TO92-CBE")
      (footprint "eagle-import:TO92-CBE")
      (libsource (lib "eagle-import") (part "-NPN-TO92-CBEMPS2222A"))
    )
    (comp (ref "T40")
      (value "MPS2222A-NPN-TO92-CBE")
      (footprint "eagle-import:TO92-CBE")
      (libsource (lib "eagle-import") (part "-NPN-TO92-CBEMPS2222A"))
    )
    (comp (ref "T41")
      (value "MPS2222A-NPN-TO92-CBE")
      (footprint "eagle-import:TO92-CBE")
      (libsource (lib "eagle-import") (part "-NPN-TO92-CBEMPS2222A"))
    )
    (comp (ref "T42")
      (value "MPS2222A-NPN-TO92-CBE")
      (footprint "eagle-import:TO92-CBE")
      (libsource (lib "eagle-import") (part "-NPN-TO92-CBEMPS2222A"))
    )
    (comp (ref "T43")
      (value "MPS2222A-NPN-TO92-CBE")
      (footprint "eagle-import:TO92-CBE")
      (libsource (lib "eagle-import") (part "-NPN-TO92-CBEMPS2222A"))
    )
    (comp (ref "T44")
      (value "MPS2222A-NPN-TO92-CBE")
      (footprint "eagle-import:TO92-CBE")
      (libsource (lib "eagle-import") (part "-NPN-TO92-CBEMPS2222A"))
    )
    (comp (ref "T45")
      (value "MPS2222A-NPN-TO92-CBE")
      (footprint "eagle-import:TO92-CBE")
      (libsource (lib "eagle-import") (part "-NPN-TO92-CBEMPS2222A"))
    )
    (comp (ref "T46")
      (value "MPS2222A-NPN-TO92-CBE")
      (footprint "eagle-import:TO92-CBE")
      (libsource (lib "eagle-import") (part "-NPN-TO92-CBEMPS2222A"))
    )
    (comp (ref "T47")
      (value "MPS2222A-NPN-TO92-CBE")
      (footprint "eagle-import:TO92-CBE")
      (libsource (lib "eagle-import") (part "-NPN-TO92-CBEMPS2222A"))
    )
    (comp (ref "T48")
      (value "MPS2222A-NPN-TO92-CBE")
      (footprint "eagle-import:TO92-CBE")
      (libsource (lib "eagle-import") (part "-NPN-TO92-CBEMPS2222A"))
    )
    (comp (ref "T49")
      (value "MPS2222A-NPN-TO92-CBE")
      (footprint "eagle-import:TO92-CBE")
      (libsource (lib "eagle-import") (part "-NPN-TO92-CBEMPS2222A"))
    )
    (comp (ref "T50")
      (value "MPS2222A-NPN-TO92-CBE")
      (footprint "eagle-import:TO92-CBE")
      (libsource (lib "eagle-import") (part "-NPN-TO92-CBEMPS2222A"))
    )
    (comp (ref "T51")
      (value "MPS2222A-NPN-TO92-CBE")
      (footprint "eagle-import:TO92-CBE")
      (libsource (lib "eagle-import") (part "-NPN-TO92-CBEMPS2222A"))
    )
    (comp (ref "T52")
      (value "MPS2222A-NPN-TO92-CBE")
      (footprint "eagle-import:TO92-CBE")
      (libsource (lib "eagle-import") (part "-NPN-TO92-CBEMPS2222A"))
    )
    (comp (ref "T53")
      (value "MPS2222A-NPN-TO92-CBE")
      (footprint "eagle-import:TO92-CBE")
      (libsource (lib "eagle-import") (part "-NPN-TO92-CBEMPS2222A"))
    )
    (comp (ref "T54")
      (value "MPS2222A-NPN-TO92-CBE")
      (footprint "eagle-import:TO92-CBE")
      (libsource (lib "eagle-import") (part "-NPN-TO92-CBEMPS2222A"))
    )
    (comp (ref "T55")
      (value "MPS2222A-NPN-TO92-CBE")
      (footprint "eagle-import:TO92-CBE")
      (libsource (lib "eagle-import") (part "-NPN-TO92-CBEMPS2222A"))
    )
    (comp (ref "T56")
      (value "MPS2222A-NPN-TO92-CBE")
      (footprint "eagle-import:TO92-CBE")
      (libsource (lib "eagle-import") (part "-NPN-TO92-CBEMPS2222A"))
    )
    (comp (ref "T57")
      (value "MPS2222A-NPN-TO92-CBE")
      (footprint "eagle-import:TO92-CBE")
      (libsource (lib "eagle-import") (part "-NPN-TO92-CBEMPS2222A"))
    )
    (comp (ref "T58")
      (value "MPS2222A-NPN-TO92-CBE")
      (footprint "eagle-import:TO92-CBE")
      (libsource (lib "eagle-import") (part "-NPN-TO92-CBEMPS2222A"))
    )
    (comp (ref "T59")
      (value "MPS2222A-NPN-TO92-CBE")
      (footprint "eagle-import:TO92-CBE")
      (libsource (lib "eagle-import") (part "-NPN-TO92-CBEMPS2222A"))
    )
    (comp (ref "T60")
      (value "MPS2222A-NPN-TO92-CBE")
      (footprint "eagle-import:TO92-CBE")
      (libsource (lib "eagle-import") (part "-NPN-TO92-CBEMPS2222A"))
    )
    (comp (ref "T61")
      (value "MPS2222A-NPN-TO92-CBE")
      (footprint "eagle-import:TO92-CBE")
      (libsource (lib "eagle-import") (part "-NPN-TO92-CBEMPS2222A"))
    )
    (comp (ref "T62")
      (value "MPS2222A-NPN-TO92-CBE")
      (footprint "eagle-import:TO92-CBE")
      (libsource (lib "eagle-import") (part "-NPN-TO92-CBEMPS2222A"))
    )
    (comp (ref "T63")
      (value "MPS2222A-NPN-TO92-CBE")
      (footprint "eagle-import:TO92-CBE")
      (libsource (lib "eagle-import") (part "-NPN-TO92-CBEMPS2222A"))
    )
    (comp (ref "T64")
      (value "MPS2222A-NPN-TO92-CBE")
      (footprint "eagle-import:TO92-CBE")
      (libsource (lib "eagle-import") (part "-NPN-TO92-CBEMPS2222A"))
    )
    (comp (ref "T65")
      (value "MPS2222A-NPN-TO92-CBE")
      (footprint "eagle-import:TO92-CBE")
      (libsource (lib "eagle-import") (part "-NPN-TO92-CBEMPS2222A"))
    )
    (comp (ref "T66")
      (value "MPS2222A-NPN-TO92-CBE")
      (footprint "eagle-import:TO92-CBE")
      (libsource (lib "eagle-import") (part "-NPN-TO92-CBEMPS2222A"))
    )
    (comp (ref "T67")
      (value "MPS2222A-NPN-TO92-CBE")
      (footprint "eagle-import:TO92-CBE")
      (libsource (lib "eagle-import") (part "-NPN-TO92-CBEMPS2222A"))
    )
    (comp (ref "T68")
      (value "MPS2222A-NPN-TO92-CBE")
      (footprint "eagle-import:TO92-CBE")
      (libsource (lib "eagle-import") (part "-NPN-TO92-CBEMPS2222A"))
    )
    (comp (ref "T69")
      (value "MPS2222A-NPN-TO92-CBE")
      (footprint "eagle-import:TO92-CBE")
      (libsource (lib "eagle-import") (part "-NPN-TO92-CBEMPS2222A"))
    )
    (comp (ref "T70")
      (value "MPS2222A-NPN-TO92-CBE")
      (footprint "eagle-import:TO92-CBE")
      (libsource (lib "eagle-import") (part "-NPN-TO92-CBEMPS2222A"))
    )
    (comp (ref "T71")
      (value "MPS2222A-NPN-TO92-CBE")
      (footprint "eagle-import:TO92-CBE")
      (libsource (lib "eagle-import") (part "-NPN-TO92-CBEMPS2222A"))
    )
    (comp (ref "T72")
      (value "MPS2222A-NPN-TO92-CBE")
      (footprint "eagle-import:TO92-CBE")
      (libsource (lib "eagle-import") (part "-NPN-TO92-CBEMPS2222A"))
    )
    (comp (ref "T73")
      (value "MPS2222A-NPN-TO92-CBE")
      (footprint "eagle-import:TO92-CBE")
      (libsource (lib "eagle-import") (part "-NPN-TO92-CBEMPS2222A"))
    )
    (comp (ref "T74")
      (value "MPS2222A-NPN-TO92-CBE")
      (footprint "eagle-import:TO92-CBE")
      (libsource (lib "eagle-import") (part "-NPN-TO92-CBEMPS2222A"))
    )
    (comp (ref "T75")
      (value "MPS2222A-NPN-TO92-CBE")
      (footprint "eagle-import:TO92-CBE")
      (libsource (lib "eagle-import") (part "-NPN-TO92-CBEMPS2222A"))
    )
    (comp (ref "T76")
      (value "MPS2222A-NPN-TO92-CBE")
      (footprint "eagle-import:TO92-CBE")
      (libsource (lib "eagle-import") (part "-NPN-TO92-CBEMPS2222A"))
    )
    (comp (ref "T77")
      (value "MPS2222A-NPN-TO92-CBE")
      (footprint "eagle-import:TO92-CBE")
      (libsource (lib "eagle-import") (part "-NPN-TO92-CBEMPS2222A"))
    )
    (comp (ref "T78")
      (value "MPS2222A-NPN-TO92-CBE")
      (footprint "eagle-import:TO92-CBE")
      (libsource (lib "eagle-import") (part "-NPN-TO92-CBEMPS2222A"))
    )
    (comp (ref "T79")
      (value "MPS2222A-NPN-TO92-CBE")
      (footprint "eagle-import:TO92-CBE")
      (libsource (lib "eagle-import") (part "-NPN-TO92-CBEMPS2222A"))
    )
    (comp (ref "T80")
      (value "MPS2222A-NPN-TO92-CBE")
      (footprint "eagle-import:TO92-CBE")
      (libsource (lib "eagle-import") (part "-NPN-TO92-CBEMPS2222A"))
    )
    (comp (ref "T81")
      (value "MPS2222A-NPN-TO92-CBE")
      (footprint "eagle-import:TO92-CBE")
      (libsource (lib "eagle-import") (part "-NPN-TO92-CBEMPS2222A"))
    )
    (comp (ref "T82")
      (value "MPS2222A-NPN-TO92-CBE")
      (footprint "eagle-import:TO92-CBE")
      (libsource (lib "eagle-import") (part "-NPN-TO92-CBEMPS2222A"))
    )
    (comp (ref "T83")
      (value "MPS2222A-NPN-TO92-CBE")
      (footprint "eagle-import:TO92-CBE")
      (libsource (lib "eagle-import") (part "-NPN-TO92-CBEMPS2222A"))
    )
    (comp (ref "T84")
      (value "MPS2222A-NPN-TO92-CBE")
      (footprint "eagle-import:TO92-CBE")
      (libsource (lib "eagle-import") (part "-NPN-TO92-CBEMPS2222A"))
    )
    (comp (ref "T85")
      (value "MPS2222A-NPN-TO92-CBE")
      (footprint "eagle-import:TO92-CBE")
      (libsource (lib "eagle-import") (part "-NPN-TO92-CBEMPS2222A"))
    )
    (comp (ref "T86")
      (value "MPS2222A-NPN-TO92-CBE")
      (footprint "eagle-import:TO92-CBE")
      (libsource (lib "eagle-import") (part "-NPN-TO92-CBEMPS2222A"))
    )
    (comp (ref "T87")
      (value "MPS2222A-NPN-TO92-CBE")
      (footprint "eagle-import:TO92-CBE")
      (libsource (lib "eagle-import") (part "-NPN-TO92-CBEMPS2222A"))
    )
    (comp (ref "T88")
      (value "MPS2222A-NPN-TO92-CBE")
      (footprint "eagle-import:TO92-CBE")
      (libsource (lib "eagle-import") (part "-NPN-TO92-CBEMPS2222A"))
    )
    (comp (ref "T89")
      (value "MPS2222A-NPN-TO92-CBE")
      (footprint "eagle-import:TO92-CBE")
      (libsource (lib "eagle-import") (part "-NPN-TO92-CBEMPS2222A"))
    )
    (comp (ref "TAD")
      (value "BULB")
      (footprint "eagle-import:BULB")
      (libsource (lib "eagle-import") (part "BULB"))
    )
    (comp (ref "WORDCOUNT")
      (value "BULB")
      (footprint "eagle-import:BULB")
      (libsource (lib "eagle-import") (part "BULB"))
    )
    (comp (ref "C40")
      (value "MA17-2")
      (footprint "eagle-import:MA17-2")
      (libsource (lib "eagle-import") (part "MA17-2"))
    )
    (comp (ref "D40")
      (value "MA17-2")
      (footprint "eagle-import:MA17-2")
      (libsource (lib "eagle-import") (part "MA17-2"))
    )
    (comp (ref "E40")
      (value "MA17-2")
      (footprint "eagle-import:MA17-2")
      (libsource (lib "eagle-import") (part "MA17-2"))
    )
    (comp (ref "F40")
      (value "MA17-2")
      (footprint "eagle-import:MA17-2")
      (libsource (lib "eagle-import") (part "MA17-2"))
    )
  )
  (nets
    (net (code "1") (name "+15V") (class "Default")
      (node (ref "+V1") (pin "1") (pinfunction "1_1") (pintype "passive"))
      (node (ref "+V2") (pin "1") (pinfunction "1_1") (pintype "passive"))
      (node (ref "+V3") (pin "1") (pinfunction "1_1") (pintype "passive"))
      (node (ref "+V4") (pin "1") (pinfunction "1_1") (pintype "passive"))
      (node (ref "R1") (pin "1") (pinfunction "1_1") (pintype "passive"))
      (node (ref "R10") (pin "1") (pinfunction "1_1") (pintype "passive"))
      (node (ref "R11") (pin "1") (pinfunction "1_1") (pintype "passive"))
      (node (ref "R12") (pin "1") (pinfunction "1_1") (pintype "passive"))
      (node (ref "R13") (pin "1") (pinfunction "1_1") (pintype "passive"))
      (node (ref "R14") (pin "1") (pinfunction "1_1") (pintype "passive"))
      (node (ref "R15") (pin "1") (pinfunction "1_1") (pintype "passive"))
      (node (ref "R16") (pin "1") (pinfunction "1_1") (pintype "passive"))
      (node (ref "R17") (pin "1") (pinfunction "1_1") (pintype "passive"))
      (node (ref "R18") (pin "1") (pinfunction "1_1") (pintype "passive"))
      (node (ref "R19") (pin "1") (pinfunction "1_1") (pintype "passive"))
      (node (ref "R2") (pin "1") (pinfunction "1_1") (pintype "passive"))
      (node (ref "R20") (pin "1") (pinfunction "1_1") (pintype "passive"))
      (node (ref "R21") (pin "1") (pinfunction "1_1") (pintype "passive"))
      (node (ref "R22") (pin "1") (pinfunction "1_1") (pintype "passive"))
      (node (ref "R23") (pin "1") (pinfunction "1_1") (pintype "passive"))
      (node (ref "R24") (pin "1") (pinfunction "1_1") (pintype "passive"))
      (node (ref "R25") (pin "1") (pinfunction "1_1") (pintype "passive"))
      (node (ref "R26") (pin "1") (pinfunction "1_1") (pintype "passive"))
      (node (ref "R27") (pin "1") (pinfunction "1_1") (pintype "passive"))
      (node (ref "R28") (pin "1") (pinfunction "1_1") (pintype "passive"))
      (node (ref "R29") (pin "1") (pinfunction "1_1") (pintype "passive"))
      (node (ref "R3") (pin "1") (pinfunction "1_1") (pintype "passive"))
      (node (ref "R30") (pin "1") (pinfunction "1_1") (pintype "passive"))
      (node (ref "R31") (pin "1") (pinfunction "1_1") (pintype "passive"))
      (node (ref "R32") (pin "1") (pinfunction "1_1") (pintype "passive"))
      (node (ref "R33") (pin "1") (pinfunction "1_1") (pintype "passive"))
      (node (ref "R34") (pin "1") (pinfunction "1_1") (pintype "passive"))
      (node (ref "R35") (pin "1") (pinfunction "1_1") (pintype "passive"))
      (node (ref "R36") (pin "1") (pinfunction "1_1") (pintype "passive"))
      (node (ref "R37") (pin "1") (pinfunction "1_1") (pintype "passive"))
      (node (ref "R38") (pin "1") (pinfunction "1_1") (pintype "passive"))
      (node (ref "R39") (pin "1") (pinfunction "1_1") (pintype "passive"))
      (node (ref "R4") (pin "1") (pinfunction "1_1") (pintype "passive"))
      (node (ref "R40") (pin "1") (pinfunction "1_1") (pintype "passive"))
      (node (ref "R41") (pin "1") (pinfunction "1_1") (pintype "passive"))
      (node (ref "R42") (pin "1") (pinfunction "1_1") (pintype "passive"))
      (node (ref "R43") (pin "1") (pinfunction "1_1") (pintype "passive"))
      (node (ref "R44") (pin "1") (pinfunction "1_1") (pintype "passive"))
      (node (ref "R45") (pin "1") (pinfunction "1_1") (pintype "passive"))
      (node (ref "R46") (pin "1") (pinfunction "1_1") (pintype "passive"))
      (node (ref "R47") (pin "1") (pinfunction "1_1") (pintype "passive"))
      (node (ref "R48") (pin "1") (pinfunction "1_1") (pintype "passive"))
      (node (ref "R49") (pin "1") (pinfunction "1_1") (pintype "passive"))
      (node (ref "R5") (pin "1") (pinfunction "1_1") (pintype "passive"))
      (node (ref "R50") (pin "1") (pinfunction "1_1") (pintype "passive"))
      (node (ref "R51") (pin "1") (pinfunction "1_1") (pintype "passive"))
      (node (ref "R52") (pin "1") (pinfunction "1_1") (pintype "passive"))
      (node (ref "R53") (pin "1") (pinfunction "1_1") (pintype "passive"))
      (node (ref "R54") (pin "1") (pinfunction "1_1") (pintype "passive"))
      (node (ref "R55") (pin "1") (pinfunction "1_1") (pintype "passive"))
      (node (ref "R56") (pin "1") (pinfunction "1_1") (pintype "passive"))
      (node (ref "R57") (pin "1") (pinfunction "1_1") (pintype "passive"))
      (node (ref "R58") (pin "1") (pinfunction "1_1") (pintype "passive"))
      (node (ref "R59") (pin "1") (pinfunction "1_1") (pintype "passive"))
      (node (ref "R6") (pin "1") (pinfunction "1_1") (pintype "passive"))
      (node (ref "R60") (pin "1") (pinfunction "1_1") (pintype "passive"))
      (node (ref "R61") (pin "1") (pinfunction "1_1") (pintype "passive"))
      (node (ref "R62") (pin "1") (pinfunction "1_1") (pintype "passive"))
      (node (ref "R63") (pin "1") (pinfunction "1_1") (pintype "passive"))
      (node (ref "R64") (pin "1") (pinfunction "1_1") (pintype "passive"))
      (node (ref "R65") (pin "1") (pinfunction "1_1") (pintype "passive"))
      (node (ref "R66") (pin "1") (pinfunction "1_1") (pintype "passive"))
      (node (ref "R67") (pin "1") (pinfunction "1_1") (pintype "passive"))
      (node (ref "R68") (pin "1") (pinfunction "1_1") (pintype "passive"))
      (node (ref "R69") (pin "1") (pinfunction "1_1") (pintype "passive"))
      (node (ref "R7") (pin "1") (pinfunction "1_1") (pintype "passive"))
      (node (ref "R70") (pin "1") (pinfunction "1_1") (pintype "passive"))
      (node (ref "R71") (pin "1") (pinfunction "1_1") (pintype "passive"))
      (node (ref "R72") (pin "1") (pinfunction "1_1") (pintype "passive"))
      (node (ref "R73") (pin "1") (pinfunction "1_1") (pintype "passive"))
      (node (ref "R74") (pin "1") (pinfunction "1_1") (pintype "passive"))
      (node (ref "R75") (pin "1") (pinfunction "1_1") (pintype "passive"))
      (node (ref "R76") (pin "1") (pinfunction "1_1") (pintype "passive"))
      (node (ref "R77") (pin "1") (pinfunction "1_1") (pintype "passive"))
      (node (ref "R78") (pin "1") (pinfunction "1_1") (pintype "passive"))
      (node (ref "R79") (pin "1") (pinfunction "1_1") (pintype "passive"))
      (node (ref "R8") (pin "1") (pinfunction "1_1") (pintype "passive"))
      (node (ref "R80") (pin "1") (pinfunction "1_1") (pintype "passive"))
      (node (ref "R81") (pin "1") (pinfunction "1_1") (pintype "passive"))
      (node (ref "R82") (pin "1") (pinfunction "1_1") (pintype "passive"))
      (node (ref "R83") (pin "1") (pinfunction "1_1") (pintype "passive"))
      (node (ref "R84") (pin "1") (pinfunction "1_1") (pintype "passive"))
      (node (ref "R85") (pin "1") (pinfunction "1_1") (pintype "passive"))
      (node (ref "R86") (pin "1") (pinfunction "1_1") (pintype "passive"))
      (node (ref "R87") (pin "1") (pinfunction "1_1") (pintype "passive"))
      (node (ref "R88") (pin "1") (pinfunction "1_1") (pintype "passive"))
      (node (ref "R89") (pin "1") (pinfunction "1_1") (pintype "passive"))
      (node (ref "R9") (pin "1") (pinfunction "1_1") (pintype "passive"))
    )
    (net (code "2") (name "AC0") (class "Default")
      (node (ref "D40TOP") (pin "4") (pinfunction "1_4") (pintype "passive"))
      (node (ref "E40") (pin "7") (pinfunction "7_7") (pintype "passive"))
      (node (ref "T43") (pin "B") (pinfunction "B_B") (pintype "passive"))
    )
    (net (code "3") (name "AC1") (class "Default")
      (node (ref "D40BOT") (pin "2") (pinfunction "1_2") (pintype "passive"))
      (node (ref "E40") (pin "4") (pinfunction "4_4") (pintype "passive"))
      (node (ref "T44") (pin "B") (pinfunction "B_B") (pintype "passive"))
    )
    (net (code "4") (name "AC2") (class "Default")
      (node (ref "D40TOP") (pin "12") (pinfunction "1_12") (pintype "passive"))
      (node (ref "E40") (pin "21") (pinfunction "21_21") (pintype "passive"))
      (node (ref "T45") (pin "B") (pinfunction "B_B") (pintype "passive"))
    )
    (net (code "5") (name "AC3") (class "Default")
      (node (ref "D40BOT") (pin "9") (pinfunction "1_9") (pintype "passive"))
      (node (ref "E40") (pin "14") (pinfunction "14_14") (pintype "passive"))
      (node (ref "T46") (pin "B") (pinfunction "B_B") (pintype "passive"))
    )
    (net (code "6") (name "AC4") (class "Default")
      (node (ref "D40TOP") (pin "17") (pinfunction "1_17") (pintype "passive"))
      (node (ref "E40") (pin "31") (pinfunction "31_31") (pintype "passive"))
      (node (ref "T47") (pin "B") (pinfunction "B_B") (pintype "passive"))
    )
    (net (code "7") (name "AC5") (class "Default")
      (node (ref "D40BOT") (pin "16") (pinfunction "1_16") (pintype "passive"))
      (node (ref "E40") (pin "28") (pinfunction "28_28") (pintype "passive"))
      (node (ref "T48") (pin "B") (pinfunction "B_B") (pintype "passive"))
    )
    (net (code "8") (name "AC6") (class "Default")
      (node (ref "E40TOP") (pin "4") (pinfunction "1_4") (pintype "passive"))
      (node (ref "F40") (pin "7") (pinfunction "7_7") (pintype "passive"))
      (node (ref "T49") (pin "B") (pinfunction "B_B") (pintype "passive"))
    )
    (net (code "9") (name "AC7") (class "Default")
      (node (ref "E40BOT") (pin "2") (pinfunction "1_2") (pintype "passive"))
      (node (ref "F40") (pin "4") (pinfunction "4_4") (pintype "passive"))
      (node (ref "T50") (pin "B") (pinfunction "B_B") (pintype "passive"))
    )
    (net (code "10") (name "AC8") (class "Default")
      (node (ref "E40TOP") (pin "12") (pinfunction "1_12") (pintype "passive"))
      (node (ref "F40") (pin "21") (pinfunction "21_21") (pintype "passive"))
      (node (ref "T51") (pin "B") (pinfunction "B_B") (pintype "passive"))
    )
    (net (code "11") (name "AC9") (class "Default")
      (node (ref "E40BOT") (pin "9") (pinfunction "1_9") (pintype "passive"))
      (node (ref "F40") (pin "14") (pinfunction "14_14") (pintype "passive"))
      (node (ref "T52") (pin "B") (pinfunction "B_B") (pintype "passive"))
    )
    (net (code "12") (name "AC10") (class "Default")
      (node (ref "E40TOP") (pin "17") (pinfunction "1_17") (pintype "passive"))
      (node (ref "F40") (pin "31") (pinfunction "31_31") (pintype "passive"))
      (node (ref "T53") (pin "B") (pinfunction "B_B") (pintype "passive"))
    )
    (net (code "13") (name "AC11") (class "Default")
      (node (ref "E40BOT") (pin "16") (pinfunction "1_16") (pintype "passive"))
      (node (ref "F40") (pin "28") (pinfunction "28_28") (pintype "passive"))
      (node (ref "T54") (pin "B") (pinfunction "B_B") (pintype "passive"))
    )
    (net (code "14") (name "AND") (class "Default")
      (node (ref "D40") (pin "2") (pinfunction "2_2") (pintype "passive"))
      (node (ref "F40BOT") (pin "1") (pinfunction "1_1") (pintype "passive"))
      (node (ref "T82") (pin "B") (pinfunction "B_B") (pintype "passive"))
    )
    (net (code "15") (name "BREAK") (class "Default")
      (node (ref "D40") (pin "22") (pinfunction "22_22") (pintype "passive"))
      (node (ref "F40BOT") (pin "12") (pinfunction "1_12") (pintype "passive"))
      (node (ref "T81") (pin "B") (pinfunction "B_B") (pintype "passive"))
    )
    (net (code "16") (name "CA") (class "Default")
      (node (ref "D40") (pin "32") (pinfunction "32_32") (pintype "passive"))
      (node (ref "F40BOT") (pin "18") (pinfunction "1_18") (pintype "passive"))
      (node (ref "T80") (pin "B") (pinfunction "B_B") (pintype "passive"))
    )
    (net (code "17") (name "DCA") (class "Default")
      (node (ref "D40") (pin "8") (pinfunction "8_8") (pintype "passive"))
      (node (ref "F40BOT") (pin "4") (pinfunction "1_4") (pintype "passive"))
      (node (ref "T85") (pin "B") (pinfunction "B_B") (pintype "passive"))
    )
    (net (code "18") (name "DEFER") (class "Default")
      (node (ref "D40") (pin "26") (pinfunction "26_26") (pintype "passive"))
      (node (ref "F40BOT") (pin "15") (pinfunction "1_15") (pintype "passive"))
      (node (ref "T78") (pin "B") (pinfunction "B_B") (pintype "passive"))
    )
    (net (code "19") (name "DF0") (class "Default")
      (node (ref "C40") (pin "1") (pinfunction "1_1") (pintype "passive"))
      (node (ref "C40TOP") (pin "1") (pinfunction "1_1") (pintype "passive"))
      (node (ref "T1") (pin "B") (pinfunction "B_B") (pintype "passive"))
    )
    (net (code "20") (name "DF1") (class "Default")
      (node (ref "C40") (pin "10") (pinfunction "10_10") (pintype "passive"))
      (node (ref "C40BOT") (pin "5") (pinfunction "1_5") (pintype "passive"))
      (node (ref "T2") (pin "B") (pinfunction "B_B") (pintype "passive"))
    )
    (net (code "21") (name "DF2") (class "Default")
      (node (ref "C40") (pin "11") (pinfunction "11_11") (pintype "passive"))
      (node (ref "C40TOP") (pin "6") (pinfunction "1_6") (pintype "passive"))
      (node (ref "T3") (pin "B") (pinfunction "B_B") (pintype "passive"))
    )
    (net (code "22") (name "EXECUTE") (class "Default")
      (node (ref "D40") (pin "28") (pinfunction "28_28") (pintype "passive"))
      (node (ref "F40BOT") (pin "16") (pinfunction "1_16") (pintype "passive"))
      (node (ref "T77") (pin "B") (pinfunction "B_B") (pintype "passive"))
    )
    (net (code "23") (name "FETCH") (class "Default")
      (node (ref "D40") (pin "24") (pinfunction "24_24") (pintype "passive"))
      (node (ref "F40BOT") (pin "14") (pinfunction "1_14") (pintype "passive"))
      (node (ref "T76") (pin "B") (pinfunction "B_B") (pintype "passive"))
    )
    (net (code "24") (name "GND") (class "Default")
      (node (ref "C40") (pin "17") (pinfunction "17_17") (pintype "passive"))
      (node (ref "C40") (pin "18") (pinfunction "18_18") (pintype "passive"))
      (node (ref "C40") (pin "19") (pinfunction "19_19") (pintype "passive"))
      (node (ref "C40") (pin "20") (pinfunction "20_20") (pintype "passive"))
      (node (ref "C40BOT") (pin "13") (pinfunction "1_13") (pintype "passive"))
      (node (ref "D40") (pin "17") (pinfunction "17_17") (pintype "passive"))
      (node (ref "D40") (pin "18") (pinfunction "18_18") (pintype "passive"))
      (node (ref "D40") (pin "19") (pinfunction "19_19") (pintype "passive"))
      (node (ref "D40") (pin "20") (pinfunction "20_20") (pintype "passive"))
      (node (ref "D40BOT") (pin "13") (pinfunction "1_13") (pintype "passive"))
      (node (ref "E40") (pin "17") (pinfunction "17_17") (pintype "passive"))
      (node (ref "E40") (pin "18") (pinfunction "18_18") (pintype "passive"))
      (node (ref "E40") (pin "19") (pinfunction "19_19") (pintype "passive"))
      (node (ref "E40") (pin "20") (pinfunction "20_20") (pintype "passive"))
      (node (ref "E40BOT") (pin "13") (pinfunction "1_13") (pintype "passive"))
      (node (ref "F40") (pin "17") (pinfunction "17_17") (pintype "passive"))
      (node (ref "F40") (pin "18") (pinfunction "18_18") (pintype "passive"))
      (node (ref "F40") (pin "19") (pinfunction "19_19") (pintype "passive"))
      (node (ref "F40") (pin "20") (pinfunction "20_20") (pintype "passive"))
      (node (ref "F40BOT") (pin "13") (pinfunction "1_13") (pintype "passive"))
      (node (ref "GND1") (pin "1") (pinfunction "1_1") (pintype "passive"))
      (node (ref "GND2") (pin "1") (pinfunction "1_1") (pintype "passive"))
      (node (ref "GND3") (pin "1") (pinfunction "1_1") (pintype "passive"))
      (node (ref "GND4") (pin "1") (pinfunction "1_1") (pintype "passive"))
      (node (ref "T1") (pin "E") (pinfunction "E_E") (pintype "passive"))
      (node (ref "T10") (pin "E") (pinfunction "E_E") (pintype "passive"))
      (node (ref "T11") (pin "E") (pinfunction "E_E") (pintype "passive"))
      (node (ref "T12") (pin "E") (pinfunction "E_E") (pintype "passive"))
      (node (ref "T13") (pin "E") (pinfunction "E_E") (pintype "passive"))
      (node (ref "T14") (pin "E") (pinfunction "E_E") (pintype "passive"))
      (node (ref "T15") (pin "E") (pinfunction "E_E") (pintype "passive"))
      (node (ref "T16") (pin "E") (pinfunction "E_E") (pintype "passive"))
      (node (ref "T17") (pin "E") (pinfunction "E_E") (pintype "passive"))
      (node (ref "T18") (pin "E") (pinfunction "E_E") (pintype "passive"))
      (node (ref "T19") (pin "E") (pinfunction "E_E") (pintype "passive"))
      (node (ref "T2") (pin "E") (pinfunction "E_E") (pintype "passive"))
      (node (ref "T20") (pin "E") (pinfunction "E_E") (pintype "passive"))
      (node (ref "T21") (pin "E") (pinfunction "E_E") (pintype "passive"))
      (node (ref "T22") (pin "E") (pinfunction "E_E") (pintype "passive"))
      (node (ref "T23") (pin "E") (pinfunction "E_E") (pintype "passive"))
      (node (ref "T24") (pin "E") (pinfunction "E_E") (pintype "passive"))
      (node (ref "T25") (pin "E") (pinfunction "E_E") (pintype "passive"))
      (node (ref "T26") (pin "E") (pinfunction "E_E") (pintype "passive"))
      (node (ref "T27") (pin "E") (pinfunction "E_E") (pintype "passive"))
      (node (ref "T28") (pin "E") (pinfunction "E_E") (pintype "passive"))
      (node (ref "T29") (pin "E") (pinfunction "E_E") (pintype "passive"))
      (node (ref "T3") (pin "E") (pinfunction "E_E") (pintype "passive"))
      (node (ref "T30") (pin "E") (pinfunction "E_E") (pintype "passive"))
      (node (ref "T31") (pin "E") (pinfunction "E_E") (pintype "passive"))
      (node (ref "T32") (pin "E") (pinfunction "E_E") (pintype "passive"))
      (node (ref "T33") (pin "E") (pinfunction "E_E") (pintype "passive"))
      (node (ref "T34") (pin "E") (pinfunction "E_E") (pintype "passive"))
      (node (ref "T35") (pin "E") (pinfunction "E_E") (pintype "passive"))
      (node (ref "T36") (pin "E") (pinfunction "E_E") (pintype "passive"))
      (node (ref "T37") (pin "E") (pinfunction "E_E") (pintype "passive"))
      (node (ref "T38") (pin "E") (pinfunction "E_E") (pintype "passive"))
      (node (ref "T39") (pin "E") (pinfunction "E_E") (pintype "passive"))
      (node (ref "T4") (pin "E") (pinfunction "E_E") (pintype "passive"))
      (node (ref "T40") (pin "E") (pinfunction "E_E") (pintype "passive"))
      (node (ref "T41") (pin "E") (pinfunction "E_E") (pintype "passive"))
      (node (ref "T42") (pin "E") (pinfunction "E_E") (pintype "passive"))
      (node (ref "T43") (pin "E") (pinfunction "E_E") (pintype "passive"))
      (node (ref "T44") (pin "E") (pinfunction "E_E") (pintype "passive"))
      (node (ref "T45") (pin "E") (pinfunction "E_E") (pintype "passive"))
      (node (ref "T46") (pin "E") (pinfunction "E_E") (pintype "passive"))
      (node (ref "T47") (pin "E") (pinfunction "E_E") (pintype "passive"))
      (node (ref "T48") (pin "E") (pinfunction "E_E") (pintype "passive"))
      (node (ref "T49") (pin "E") (pinfunction "E_E") (pintype "passive"))
      (node (ref "T5") (pin "E") (pinfunction "E_E") (pintype "passive"))
      (node (ref "T50") (pin "E") (pinfunction "E_E") (pintype "passive"))
      (node (ref "T51") (pin "E") (pinfunction "E_E") (pintype "passive"))
      (node (ref "T52") (pin "E") (pinfunction "E_E") (pintype "passive"))
      (node (ref "T53") (pin "E") (pinfunction "E_E") (pintype "passive"))
      (node (ref "T54") (pin "E") (pinfunction "E_E") (pintype "passive"))
      (node (ref "T55") (pin "E") (pinfunction "E_E") (pintype "passive"))
      (node (ref "T56") (pin "E") (pinfunction "E_E") (pintype "passive"))
      (node (ref "T57") (pin "E") (pinfunction "E_E") (pintype "passive"))
      (node (ref "T58") (pin "E") (pinfunction "E_E") (pintype "passive"))
      (node (ref "T59") (pin "E") (pinfunction "E_E") (pintype "passive"))
      (node (ref "T6") (pin "E") (pinfunction "E_E") (pintype "passive"))
      (node (ref "T60") (pin "E") (pinfunction "E_E") (pintype "passive"))
      (node (ref "T61") (pin "E") (pinfunction "E_E") (pintype "passive"))
      (node (ref "T62") (pin "E") (pinfunction "E_E") (pintype "passive"))
      (node (ref "T63") (pin "E") (pinfunction "E_E") (pintype "passive"))
      (node (ref "T64") (pin "E") (pinfunction "E_E") (pintype "passive"))
      (node (ref "T65") (pin "E") (pinfunction "E_E") (pintype "passive"))
      (node (ref "T66") (pin "E") (pinfunction "E_E") (pintype "passive"))
      (node (ref "T67") (pin "E") (pinfunction "E_E") (pintype "passive"))
      (node (ref "T68") (pin "E") (pinfunction "E_E") (pintype "passive"))
      (node (ref "T69") (pin "E") (pinfunction "E_E") (pintype "passive"))
      (node (ref "T7") (pin "E") (pinfunction "E_E") (pintype "passive"))
      (node (ref "T70") (pin "E") (pinfunction "E_E") (pintype "passive"))
      (node (ref "T71") (pin "E") (pinfunction "E_E") (pintype "passive"))
      (node (ref "T72") (pin "E") (pinfunction "E_E") (pintype "passive"))
      (node (ref "T73") (pin "E") (pinfunction "E_E") (pintype "passive"))
      (node (ref "T74") (pin "E") (pinfunction "E_E") (pintype "passive"))
      (node (ref "T75") (pin "E") (pinfunction "E_E") (pintype "passive"))
      (node (ref "T76") (pin "E") (pinfunction "E_E") (pintype "passive"))
      (node (ref "T77") (pin "E") (pinfunction "E_E") (pintype "passive"))
      (node (ref "T78") (pin "E") (pinfunction "E_E") (pintype "passive"))
      (node (ref "T79") (pin "E") (pinfunction "E_E") (pintype "passive"))
      (node (ref "T8") (pin "E") (pinfunction "E_E") (pintype "passive"))
      (node (ref "T80") (pin "E") (pinfunction "E_E") (pintype "passive"))
      (node (ref "T81") (pin "E") (pinfunction "E_E") (pintype "passive"))
      (node (ref "T82") (pin "E") (pinfunction "E_E") (pintype "passive"))
      (node (ref "T83") (pin "E") (pinfunction "E_E") (pintype "passive"))
      (node (ref "T84") (pin "E") (pinfunction "E_E") (pintype "passive"))
      (node (ref "T85") (pin "E") (pinfunction "E_E") (pintype "passive"))
      (node (ref "T86") (pin "E") (pinfunction "E_E") (pintype "passive"))
      (node (ref "T87") (pin "E") (pinfunction "E_E") (pintype "passive"))
      (node (ref "T88") (pin "E") (pinfunction "E_E") (pintype "passive"))
      (node (ref "T89") (pin "E") (pinfunction "E_E") (pintype "passive"))
      (node (ref "T9") (pin "E") (pinfunction "E_E") (pintype "passive"))
    )
    (net (code "25") (name "IF0") (class "Default")
      (node (ref "C40") (pin "24") (pinfunction "24_24") (pintype "passive"))
      (node (ref "C40BOT") (pin "14") (pinfunction "1_14") (pintype "passive"))
      (node (ref "T4") (pin "B") (pinfunction "B_B") (pintype "passive"))
    )
    (net (code "26") (name "IF1") (class "Default")
      (node (ref "C40") (pin "25") (pinfunction "25_25") (pintype "passive"))
      (node (ref "C40TOP") (pin "14") (pinfunction "1_14") (pintype "passive"))
      (node (ref "T5") (pin "B") (pinfunction "B_B") (pintype "passive"))
    )
    (net (code "27") (name "IF2") (class "Default")
      (node (ref "C40") (pin "34") (pinfunction "34_34") (pintype "passive"))
      (node (ref "C40BOT") (pin "19") (pinfunction "1_19") (pintype "passive"))
      (node (ref "T6") (pin "B") (pinfunction "B_B") (pintype "passive"))
    )
    (net (code "28") (name "ION") (class "Default")
      (node (ref "D40") (pin "34") (pinfunction "34_34") (pintype "passive"))
      (node (ref "F40BOT") (pin "19") (pinfunction "1_19") (pintype "passive"))
      (node (ref "T73") (pin "B") (pinfunction "B_B") (pintype "passive"))
    )
    (net (code "29") (name "IOT") (class "Default")
      (node (ref "D40") (pin "23") (pinfunction "23_23") (pintype "passive"))
      (node (ref "F40TOP") (pin "13") (pinfunction "1_13") (pintype "passive"))
      (node (ref "T88") (pin "B") (pinfunction "B_B") (pintype "passive"))
    )
    (net (code "30") (name "ISZ") (class "Default")
      (node (ref "D40") (pin "6") (pinfunction "6_6") (pintype "passive"))
      (node (ref "F40BOT") (pin "3") (pinfunction "1_3") (pintype "passive"))
      (node (ref "T84") (pin "B") (pinfunction "B_B") (pintype "passive"))
    )
    (net (code "31") (name "JMP") (class "Default")
      (node (ref "D40") (pin "12") (pinfunction "12_12") (pintype "passive"))
      (node (ref "F40BOT") (pin "6") (pinfunction "1_6") (pintype "passive"))
      (node (ref "T87") (pin "B") (pinfunction "B_B") (pintype "passive"))
    )
    (net (code "32") (name "JMS") (class "Default")
      (node (ref "D40") (pin "10") (pinfunction "10_10") (pintype "passive"))
      (node (ref "F40BOT") (pin "5") (pinfunction "1_5") (pintype "passive"))
      (node (ref "T86") (pin "B") (pinfunction "B_B") (pintype "passive"))
    )
    (net (code "33") (name "LINK") (class "Default")
      (node (ref "C40") (pin "28") (pinfunction "28_28") (pintype "passive"))
      (node (ref "C40BOT") (pin "16") (pinfunction "1_16") (pintype "passive"))
      (node (ref "T72") (pin "B") (pinfunction "B_B") (pintype "passive"))
    )
    (net (code "34") (name "MA0") (class "Default")
      (node (ref "D40TOP") (pin "2") (pinfunction "1_2") (pintype "passive"))
      (node (ref "E40") (pin "3") (pinfunction "3_3") (pintype "passive"))
      (node (ref "T19") (pin "B") (pinfunction "B_B") (pintype "passive"))
    )
    (net (code "35") (name "MA1") (class "Default")
      (node (ref "D40BOT") (pin "4") (pinfunction "1_4") (pintype "passive"))
      (node (ref "E40") (pin "8") (pinfunction "8_8") (pintype "passive"))
      (node (ref "T20") (pin "B") (pinfunction "B_B") (pintype "passive"))
    )
    (net (code "36") (name "MA2") (class "Default")
      (node (ref "D40TOP") (pin "7") (pinfunction "1_7") (pintype "passive"))
      (node (ref "E40") (pin "13") (pinfunction "13_13") (pintype "passive"))
      (node (ref "T21") (pin "B") (pinfunction "B_B") (pintype "passive"))
    )
    (net (code "37") (name "MA3") (class "Default")
      (node (ref "D40BOT") (pin "12") (pinfunction "1_12") (pintype "passive"))
      (node (ref "E40") (pin "22") (pinfunction "22_22") (pintype "passive"))
      (node (ref "T22") (pin "B") (pinfunction "B_B") (pintype "passive"))
    )
    (net (code "38") (name "MA4") (class "Default")
      (node (ref "D40TOP") (pin "15") (pinfunction "1_15") (pintype "passive"))
      (node (ref "E40") (pin "27") (pinfunction "27_27") (pintype "passive"))
      (node (ref "T23") (pin "B") (pinfunction "B_B") (pintype "passive"))
    )
    (net (code "39") (name "MA5") (class "Default")
      (node (ref "D40BOT") (pin "18") (pinfunction "1_18") (pintype "passive"))
      (node (ref "E40") (pin "32") (pinfunction "32_32") (pintype "passive"))
      (node (ref "T24") (pin "B") (pinfunction "B_B") (pintype "passive"))
    )
    (net (code "40") (name "MA6") (class "Default")
      (node (ref "E40TOP") (pin "2") (pinfunction "1_2") (pintype "passive"))
      (node (ref "F40") (pin "3") (pinfunction "3_3") (pintype "passive"))
      (node (ref "T25") (pin "B") (pinfunction "B_B") (pintype "passive"))
    )
    (net (code "41") (name "MA7") (class "Default")
      (node (ref "E40BOT") (pin "4") (pinfunction "1_4") (pintype "passive"))
      (node (ref "F40") (pin "8") (pinfunction "8_8") (pintype "passive"))
      (node (ref "T26") (pin "B") (pinfunction "B_B") (pintype "passive"))
    )
    (net (code "42") (name "MA8") (class "Default")
      (node (ref "E40TOP") (pin "7") (pinfunction "1_7") (pintype "passive"))
      (node (ref "F40") (pin "13") (pinfunction "13_13") (pintype "passive"))
      (node (ref "T27") (pin "B") (pinfunction "B_B") (pintype "passive"))
    )
    (net (code "43") (name "MA9") (class "Default")
      (node (ref "E40BOT") (pin "12") (pinfunction "1_12") (pintype "passive"))
      (node (ref "F40") (pin "22") (pinfunction "22_22") (pintype "passive"))
      (node (ref "T28") (pin "B") (pinfunction "B_B") (pintype "passive"))
    )
    (net (code "44") (name "MA10") (class "Default")
      (node (ref "E40TOP") (pin "15") (pinfunction "1_15") (pintype "passive"))
      (node (ref "F40") (pin "27") (pinfunction "27_27") (pintype "passive"))
      (node (ref "T29") (pin "B") (pinfunction "B_B") (pintype "passive"))
    )
    (net (code "45") (name "MA11") (class "Default")
      (node (ref "E40BOT") (pin "18") (pinfunction "1_18") (pintype "passive"))
      (node (ref "F40") (pin "32") (pinfunction "32_32") (pintype "passive"))
      (node (ref "T30") (pin "B") (pinfunction "B_B") (pintype "passive"))
    )
    (net (code "46") (name "MB0") (class "Default")
      (node (ref "D40TOP") (pin "3") (pinfunction "1_3") (pintype "passive"))
      (node (ref "E40") (pin "5") (pinfunction "5_5") (pintype "passive"))
      (node (ref "T31") (pin "B") (pinfunction "B_B") (pintype "passive"))
    )
    (net (code "47") (name "MB1") (class "Default")
      (node (ref "D40BOT") (pin "3") (pinfunction "1_3") (pintype "passive"))
      (node (ref "E40") (pin "6") (pinfunction "6_6") (pintype "passive"))
      (node (ref "T32") (pin "B") (pinfunction "B_B") (pintype "passive"))
    )
    (net (code "48") (name "MB2") (class "Default")
      (node (ref "D40TOP") (pin "8") (pinfunction "1_8") (pintype "passive"))
      (node (ref "E40") (pin "15") (pinfunction "15_15") (pintype "passive"))
      (node (ref "T33") (pin "B") (pinfunction "B_B") (pintype "passive"))
    )
    (net (code "49") (name "MB3") (class "Default")
      (node (ref "D40BOT") (pin "11") (pinfunction "1_11") (pintype "passive"))
      (node (ref "E40") (pin "16") (pinfunction "16_16") (pintype "passive"))
      (node (ref "T34") (pin "B") (pinfunction "B_B") (pintype "passive"))
    )
    (net (code "50") (name "MB4") (class "Default")
      (node (ref "D40TOP") (pin "16") (pinfunction "1_16") (pintype "passive"))
      (node (ref "E40") (pin "29") (pinfunction "29_29") (pintype "passive"))
      (node (ref "T35") (pin "B") (pinfunction "B_B") (pintype "passive"))
    )
    (net (code "51") (name "MB5") (class "Default")
      (node (ref "D40BOT") (pin "17") (pinfunction "1_17") (pintype "passive"))
      (node (ref "E40") (pin "30") (pinfunction "30_30") (pintype "passive"))
      (node (ref "T36") (pin "B") (pinfunction "B_B") (pintype "passive"))
    )
    (net (code "52") (name "MB6") (class "Default")
      (node (ref "E40TOP") (pin "3") (pinfunction "1_3") (pintype "passive"))
      (node (ref "F40") (pin "5") (pinfunction "5_5") (pintype "passive"))
      (node (ref "T37") (pin "B") (pinfunction "B_B") (pintype "passive"))
    )
    (net (code "53") (name "MB7") (class "Default")
      (node (ref "E40BOT") (pin "3") (pinfunction "1_3") (pintype "passive"))
      (node (ref "F40") (pin "6") (pinfunction "6_6") (pintype "passive"))
      (node (ref "T38") (pin "B") (pinfunction "B_B") (pintype "passive"))
    )
    (net (code "54") (name "MB8") (class "Default")
      (node (ref "E40TOP") (pin "8") (pinfunction "1_8") (pintype "passive"))
      (node (ref "F40") (pin "15") (pinfunction "15_15") (pintype "passive"))
      (node (ref "T39") (pin "B") (pinfunction "B_B") (pintype "passive"))
    )
    (net (code "55") (name "MB9") (class "Default")
      (node (ref "E40BOT") (pin "11") (pinfunction "1_11") (pintype "passive"))
      (node (ref "F40") (pin "16") (pinfunction "16_16") (pintype "passive"))
      (node (ref "T40") (pin "B") (pinfunction "B_B") (pintype "passive"))
    )
    (net (code "56") (name "MB10") (class "Default")
      (node (ref "E40TOP") (pin "16") (pinfunction "1_16") (pintype "passive"))
      (node (ref "F40") (pin "29") (pinfunction "29_29") (pintype "passive"))
      (node (ref "T41") (pin "B") (pinfunction "B_B") (pintype "passive"))
    )
    (net (code "57") (name "MB11") (class "Default")
      (node (ref "E40BOT") (pin "17") (pinfunction "1_17") (pintype "passive"))
      (node (ref "F40") (pin "30") (pinfunction "30_30") (pintype "passive"))
      (node (ref "T42") (pin "B") (pinfunction "B_B") (pintype "passive"))
    )
    (net (code "58") (name "MQ0") (class "Default")
      (node (ref "D40TOP") (pin "5") (pinfunction "1_5") (pintype "passive"))
      (node (ref "E40") (pin "9") (pinfunction "9_9") (pintype "passive"))
      (node (ref "T55") (pin "B") (pinfunction "B_B") (pintype "passive"))
    )
    (net (code "59") (name "MQ1") (class "Default")
      (node (ref "D40BOT") (pin "1") (pinfunction "1_1") (pintype "passive"))
      (node (ref "E40") (pin "2") (pinfunction "2_2") (pintype "passive"))
      (node (ref "T56") (pin "B") (pinfunction "B_B") (pintype "passive"))
    )
    (net (code "60") (name "MQ2") (class "Default")
      (node (ref "D40TOP") (pin "13") (pinfunction "1_13") (pintype "passive"))
      (node (ref "E40") (pin "23") (pinfunction "23_23") (pintype "passive"))
      (node (ref "T57") (pin "B") (pinfunction "B_B") (pintype "passive"))
    )
    (net (code "61") (name "MQ3") (class "Default")
      (node (ref "D40BOT") (pin "6") (pinfunction "1_6") (pintype "passive"))
      (node (ref "E40") (pin "12") (pinfunction "12_12") (pintype "passive"))
      (node (ref "T58") (pin "B") (pinfunction "B_B") (pintype "passive"))
    )
    (net (code "62") (name "MQ4") (class "Default")
      (node (ref "D40TOP") (pin "18") (pinfunction "1_18") (pintype "passive"))
      (node (ref "E40") (pin "33") (pinfunction "33_33") (pintype "passive"))
      (node (ref "T59") (pin "B") (pinfunction "B_B") (pintype "passive"))
    )
    (net (code "63") (name "MQ5") (class "Default")
      (node (ref "D40BOT") (pin "15") (pinfunction "1_15") (pintype "passive"))
      (node (ref "E40") (pin "26") (pinfunction "26_26") (pintype "passive"))
      (node (ref "T60") (pin "B") (pinfunction "B_B") (pintype "passive"))
    )
    (net (code "64") (name "MQ6") (class "Default")
      (node (ref "E40TOP") (pin "5") (pinfunction "1_5") (pintype "passive"))
      (node (ref "F40") (pin "9") (pinfunction "9_9") (pintype "passive"))
      (node (ref "T61") (pin "B") (pinfunction "B_B") (pintype "passive"))
    )
    (net (code "65") (name "MQ7") (class "Default")
      (node (ref "E40BOT") (pin "1") (pinfunction "1_1") (pintype "passive"))
      (node (ref "F40") (pin "2") (pinfunction "2_2") (pintype "passive"))
      (node (ref "T62") (pin "B") (pinfunction "B_B") (pintype "passive"))
    )
    (net (code "66") (name "MQ8") (class "Default")
      (node (ref "E40TOP") (pin "13") (pinfunction "1_13") (pintype "passive"))
      (node (ref "F40") (pin "23") (pinfunction "23_23") (pintype "passive"))
      (node (ref "T63") (pin "B") (pinfunction "B_B") (pintype "passive"))
    )
    (net (code "67") (name "MQ9") (class "Default")
      (node (ref "E40BOT") (pin "6") (pinfunction "1_6") (pintype "passive"))
      (node (ref "F40") (pin "12") (pinfunction "12_12") (pintype "passive"))
      (node (ref "T64") (pin "B") (pinfunction "B_B") (pintype "passive"))
    )
    (net (code "68") (name "MQ10") (class "Default")
      (node (ref "E40TOP") (pin "18") (pinfunction "1_18") (pintype "passive"))
      (node (ref "F40") (pin "33") (pinfunction "33_33") (pintype "passive"))
      (node (ref "T65") (pin "B") (pinfunction "B_B") (pintype "passive"))
    )
    (net (code "69") (name "MQ11") (class "Default")
      (node (ref "E40BOT") (pin "15") (pinfunction "1_15") (pintype "passive"))
      (node (ref "F40") (pin "26") (pinfunction "26_26") (pintype "passive"))
      (node (ref "T66") (pin "B") (pinfunction "B_B") (pintype "passive"))
    )
    (net (code "70") (name "Net-(AC0-PadA)") (class "Default")
      (node (ref "AC0") (pin "A") (pinfunction "A_A") (pintype "passive"))
      (node (ref "R43") (pin "2") (pinfunction "2_2") (pintype "passive"))
    )
    (net (code "71") (name "Net-(AC0-PadB)") (class "Default")
      (node (ref "AC0") (pin "B") (pinfunction "B_B") (pintype "passive"))
      (node (ref "T43") (pin "C") (pinfunction "C_C") (pintype "passive"))
    )
    (net (code "72") (name "Net-(AC1-PadA)") (class "Default")
      (node (ref "AC1") (pin "A") (pinfunction "A_A") (pintype "passive"))
      (node (ref "R44") (pin "2") (pinfunction "2_2") (pintype "passive"))
    )
    (net (code "73") (name "Net-(AC1-PadB)") (class "Default")
      (node (ref "AC1") (pin "B") (pinfunction "B_B") (pintype "passive"))
      (node (ref "T44") (pin "C") (pinfunction "C_C") (pintype "passive"))
    )
    (net (code "74") (name "Net-(AC2-PadA)") (class "Default")
      (node (ref "AC2") (pin "A") (pinfunction "A_A") (pintype "passive"))
      (node (ref "R45") (pin "2") (pinfunction "2_2") (pintype "passive"))
    )
    (net (code "75") (name "Net-(AC2-PadB)") (class "Default")
      (node (ref "AC2") (pin "B") (pinfunction "B_B") (pintype "passive"))
      (node (ref "T45") (pin "C") (pinfunction "C_C") (pintype "passive"))
    )
    (net (code "76") (name "Net-(AC3-PadA)") (class "Default")
      (node (ref "AC3") (pin "A") (pinfunction "A_A") (pintype "passive"))
      (node (ref "R46") (pin "2") (pinfunction "2_2") (pintype "passive"))
    )
    (net (code "77") (name "Net-(AC3-PadB)") (class "Default")
      (node (ref "AC3") (pin "B") (pinfunction "B_B") (pintype "passive"))
      (node (ref "T46") (pin "C") (pinfunction "C_C") (pintype "passive"))
    )
    (net (code "78") (name "Net-(AC4-PadA)") (class "Default")
      (node (ref "AC4") (pin "A") (pinfunction "A_A") (pintype "passive"))
      (node (ref "R47") (pin "2") (pinfunction "2_2") (pintype "passive"))
    )
    (net (code "79") (name "Net-(AC4-PadB)") (class "Default")
      (node (ref "AC4") (pin "B") (pinfunction "B_B") (pintype "passive"))
      (node (ref "T47") (pin "C") (pinfunction "C_C") (pintype "passive"))
    )
    (net (code "80") (name "Net-(AC5-PadA)") (class "Default")
      (node (ref "AC5") (pin "A") (pinfunction "A_A") (pintype "passive"))
      (node (ref "R48") (pin "2") (pinfunction "2_2") (pintype "passive"))
    )
    (net (code "81") (name "Net-(AC5-PadB)") (class "Default")
      (node (ref "AC5") (pin "B") (pinfunction "B_B") (pintype "passive"))
      (node (ref "T48") (pin "C") (pinfunction "C_C") (pintype "passive"))
    )
    (net (code "82") (name "Net-(AC6-PadA)") (class "Default")
      (node (ref "AC6") (pin "A") (pinfunction "A_A") (pintype "passive"))
      (node (ref "R49") (pin "2") (pinfunction "2_2") (pintype "passive"))
    )
    (net (code "83") (name "Net-(AC6-PadB)") (class "Default")
      (node (ref "AC6") (pin "B") (pinfunction "B_B") (pintype "passive"))
      (node (ref "T49") (pin "C") (pinfunction "C_C") (pintype "passive"))
    )
    (net (code "84") (name "Net-(AC7-PadA)") (class "Default")
      (node (ref "AC7") (pin "A") (pinfunction "A_A") (pintype "passive"))
      (node (ref "R50") (pin "2") (pinfunction "2_2") (pintype "passive"))
    )
    (net (code "85") (name "Net-(AC7-PadB)") (class "Default")
      (node (ref "AC7") (pin "B") (pinfunction "B_B") (pintype "passive"))
      (node (ref "T50") (pin "C") (pinfunction "C_C") (pintype "passive"))
    )
    (net (code "86") (name "Net-(AC8-PadA)") (class "Default")
      (node (ref "AC8") (pin "A") (pinfunction "A_A") (pintype "passive"))
      (node (ref "R51") (pin "2") (pinfunction "2_2") (pintype "passive"))
    )
    (net (code "87") (name "Net-(AC8-PadB)") (class "Default")
      (node (ref "AC8") (pin "B") (pinfunction "B_B") (pintype "passive"))
      (node (ref "T51") (pin "C") (pinfunction "C_C") (pintype "passive"))
    )
    (net (code "88") (name "Net-(AC9-PadA)") (class "Default")
      (node (ref "AC9") (pin "A") (pinfunction "A_A") (pintype "passive"))
      (node (ref "R52") (pin "2") (pinfunction "2_2") (pintype "passive"))
    )
    (net (code "89") (name "Net-(AC9-PadB)") (class "Default")
      (node (ref "AC9") (pin "B") (pinfunction "B_B") (pintype "passive"))
      (node (ref "T52") (pin "C") (pinfunction "C_C") (pintype "passive"))
    )
    (net (code "90") (name "Net-(AC10-PadA)") (class "Default")
      (node (ref "AC10") (pin "A") (pinfunction "A_A") (pintype "passive"))
      (node (ref "R53") (pin "2") (pinfunction "2_2") (pintype "passive"))
    )
    (net (code "91") (name "Net-(AC10-PadB)") (class "Default")
      (node (ref "AC10") (pin "B") (pinfunction "B_B") (pintype "passive"))
      (node (ref "T53") (pin "C") (pinfunction "C_C") (pintype "passive"))
    )
    (net (code "92") (name "Net-(AC11-PadA)") (class "Default")
      (node (ref "AC11") (pin "A") (pinfunction "A_A") (pintype "passive"))
      (node (ref "R54") (pin "2") (pinfunction "2_2") (pintype "passive"))
    )
    (net (code "93") (name "Net-(AC11-PadB)") (class "Default")
      (node (ref "AC11") (pin "B") (pinfunction "B_B") (pintype "passive"))
      (node (ref "T54") (pin "C") (pinfunction "C_C") (pintype "passive"))
    )
    (net (code "94") (name "Net-(AND-PadA)") (class "Default")
      (node (ref "AND") (pin "A") (pinfunction "A_A") (pintype "passive"))
      (node (ref "R82") (pin "2") (pinfunction "2_2") (pintype "passive"))
    )
    (net (code "95") (name "Net-(AND-PadB)") (class "Default")
      (node (ref "AND") (pin "B") (pinfunction "B_B") (pintype "passive"))
      (node (ref "T82") (pin "C") (pinfunction "C_C") (pintype "passive"))
    )
    (net (code "96") (name "Net-(BREAK-PadA)") (class "Default")
      (node (ref "BREAK") (pin "A") (pinfunction "A_A") (pintype "passive"))
      (node (ref "R81") (pin "2") (pinfunction "2_2") (pintype "passive"))
    )
    (net (code "97") (name "Net-(BREAK-PadB)") (class "Default")
      (node (ref "BREAK") (pin "B") (pinfunction "B_B") (pintype "passive"))
      (node (ref "T81") (pin "C") (pinfunction "C_C") (pintype "passive"))
    )
    (net (code "98") (name "Net-(CURRENTADDRESS-PadA)") (class "Default")
      (node (ref "CURRENTADDRESS") (pin "A") (pinfunction "A_A") (pintype "passive"))
      (node (ref "R80") (pin "2") (pinfunction "2_2") (pintype "passive"))
    )
    (net (code "99") (name "Net-(CURRENTADDRESS-PadB)") (class "Default")
      (node (ref "CURRENTADDRESS") (pin "B") (pinfunction "B_B") (pintype "passive"))
      (node (ref "T80") (pin "C") (pinfunction "C_C") (pintype "passive"))
    )
    (net (code "100") (name "Net-(DCA-PadA)") (class "Default")
      (node (ref "DCA") (pin "A") (pinfunction "A_A") (pintype "passive"))
      (node (ref "R85") (pin "2") (pinfunction "2_2") (pintype "passive"))
    )
    (net (code "101") (name "Net-(DCA-PadB)") (class "Default")
      (node (ref "DCA") (pin "B") (pinfunction "B_B") (pintype "passive"))
      (node (ref "T85") (pin "C") (pinfunction "C_C") (pintype "passive"))
    )
    (net (code "102") (name "Net-(DEFER-PadA)") (class "Default")
      (node (ref "DEFER") (pin "A") (pinfunction "A_A") (pintype "passive"))
      (node (ref "R78") (pin "2") (pinfunction "2_2") (pintype "passive"))
    )
    (net (code "103") (name "Net-(DEFER-PadB)") (class "Default")
      (node (ref "DEFER") (pin "B") (pinfunction "B_B") (pintype "passive"))
      (node (ref "T78") (pin "C") (pinfunction "C_C") (pintype "passive"))
    )
    (net (code "104") (name "Net-(DF0-PadA)") (class "Default")
      (node (ref "DF0") (pin "A") (pinfunction "A_A") (pintype "passive"))
      (node (ref "R1") (pin "2") (pinfunction "2_2") (pintype "passive"))
    )
    (net (code "105") (name "Net-(DF0-PadB)") (class "Default")
      (node (ref "DF0") (pin "B") (pinfunction "B_B") (pintype "passive"))
      (node (ref "T1") (pin "C") (pinfunction "C_C") (pintype "passive"))
    )
    (net (code "106") (name "Net-(DF1-PadA)") (class "Default")
      (node (ref "DF1") (pin "A") (pinfunction "A_A") (pintype "passive"))
      (node (ref "R2") (pin "2") (pinfunction "2_2") (pintype "passive"))
    )
    (net (code "107") (name "Net-(DF1-PadB)") (class "Default")
      (node (ref "DF1") (pin "B") (pinfunction "B_B") (pintype "passive"))
      (node (ref "T2") (pin "C") (pinfunction "C_C") (pintype "passive"))
    )
    (net (code "108") (name "Net-(DF2-PadA)") (class "Default")
      (node (ref "DF2") (pin "A") (pinfunction "A_A") (pintype "passive"))
      (node (ref "R3") (pin "2") (pinfunction "2_2") (pintype "passive"))
    )
    (net (code "109") (name "Net-(DF2-PadB)") (class "Default")
      (node (ref "DF2") (pin "B") (pinfunction "B_B") (pintype "passive"))
      (node (ref "T3") (pin "C") (pinfunction "C_C") (pintype "passive"))
    )
    (net (code "110") (name "Net-(EXECUTE-PadA)") (class "Default")
      (node (ref "EXECUTE") (pin "A") (pinfunction "A_A") (pintype "passive"))
      (node (ref "R77") (pin "2") (pinfunction "2_2") (pintype "passive"))
    )
    (net (code "111") (name "Net-(EXECUTE-PadB)") (class "Default")
      (node (ref "EXECUTE") (pin "B") (pinfunction "B_B") (pintype "passive"))
      (node (ref "T77") (pin "C") (pinfunction "C_C") (pintype "passive"))
    )
    (net (code "112") (name "Net-(FETCH-PadA)") (class "Default")
      (node (ref "FETCH") (pin "A") (pinfunction "A_A") (pintype "passive"))
      (node (ref "R76") (pin "2") (pinfunction "2_2") (pintype "passive"))
    )
    (net (code "113") (name "Net-(FETCH-PadB)") (class "Default")
      (node (ref "FETCH") (pin "B") (pinfunction "B_B") (pintype "passive"))
      (node (ref "T76") (pin "C") (pinfunction "C_C") (pintype "passive"))
    )
    (net (code "114") (name "Net-(IF0-PadA)") (class "Default")
      (node (ref "IF0") (pin "A") (pinfunction "A_A") (pintype "passive"))
      (node (ref "R4") (pin "2") (pinfunction "2_2") (pintype "passive"))
    )
    (net (code "115") (name "Net-(IF0-PadB)") (class "Default")
      (node (ref "IF0") (pin "B") (pinfunction "B_B") (pintype "passive"))
      (node (ref "T4") (pin "C") (pinfunction "C_C") (pintype "passive"))
    )
    (net (code "116") (name "Net-(IF1-PadA)") (class "Default")
      (node (ref "IF1") (pin "A") (pinfunction "A_A") (pintype "passive"))
      (node (ref "R5") (pin "2") (pinfunction "2_2") (pintype "passive"))
    )
    (net (code "117") (name "Net-(IF1-PadB)") (class "Default")
      (node (ref "IF1") (pin "B") (pinfunction "B_B") (pintype "passive"))
      (node (ref "T5") (pin "C") (pinfunction "C_C") (pintype "passive"))
    )
    (net (code "118") (name "Net-(IF2-PadA)") (class "Default")
      (node (ref "IF2") (pin "A") (pinfunction "A_A") (pintype "passive"))
      (node (ref "R6") (pin "2") (pinfunction "2_2") (pintype "passive"))
    )
    (net (code "119") (name "Net-(IF2-PadB)") (class "Default")
      (node (ref "IF2") (pin "B") (pinfunction "B_B") (pintype "passive"))
      (node (ref "T6") (pin "C") (pinfunction "C_C") (pintype "passive"))
    )
    (net (code "120") (name "Net-(ION-PadA)") (class "Default")
      (node (ref "ION") (pin "A") (pinfunction "A_A") (pintype "passive"))
      (node (ref "R73") (pin "2") (pinfunction "2_2") (pintype "passive"))
    )
    (net (code "121") (name "Net-(ION-PadB)") (class "Default")
      (node (ref "ION") (pin "B") (pinfunction "B_B") (pintype "passive"))
      (node (ref "T73") (pin "C") (pinfunction "C_C") (pintype "passive"))
    )
    (net (code "122") (name "Net-(IOT-PadA)") (class "Default")
      (node (ref "IOT") (pin "A") (pinfunction "A_A") (pintype "passive"))
      (node (ref "R88") (pin "2") (pinfunction "2_2") (pintype "passive"))
    )
    (net (code "123") (name "Net-(IOT-PadB)") (class "Default")
      (node (ref "IOT") (pin "B") (pinfunction "B_B") (pintype "passive"))
      (node (ref "T88") (pin "C") (pinfunction "C_C") (pintype "passive"))
    )
    (net (code "124") (name "Net-(ISZ-PadA)") (class "Default")
      (node (ref "ISZ") (pin "A") (pinfunction "A_A") (pintype "passive"))
      (node (ref "R84") (pin "2") (pinfunction "2_2") (pintype "passive"))
    )
    (net (code "125") (name "Net-(ISZ-PadB)") (class "Default")
      (node (ref "ISZ") (pin "B") (pinfunction "B_B") (pintype "passive"))
      (node (ref "T84") (pin "C") (pinfunction "C_C") (pintype "passive"))
    )
    (net (code "126") (name "Net-(JMP-PadA)") (class "Default")
      (node (ref "JMP") (pin "A") (pinfunction "A_A") (pintype "passive"))
      (node (ref "R87") (pin "2") (pinfunction "2_2") (pintype "passive"))
    )
    (net (code "127") (name "Net-(JMP-PadB)") (class "Default")
      (node (ref "JMP") (pin "B") (pinfunction "B_B") (pintype "passive"))
      (node (ref "T87") (pin "C") (pinfunction "C_C") (pintype "passive"))
    )
    (net (code "128") (name "Net-(JMS-PadA)") (class "Default")
      (node (ref "JMS") (pin "A") (pinfunction "A_A") (pintype "passive"))
      (node (ref "R86") (pin "2") (pinfunction "2_2") (pintype "passive"))
    )
    (net (code "129") (name "Net-(JMS-PadB)") (class "Default")
      (node (ref "JMS") (pin "B") (pinfunction "B_B") (pintype "passive"))
      (node (ref "T86") (pin "C") (pinfunction "C_C") (pintype "passive"))
    )
    (net (code "130") (name "Net-(LINK-PadA)") (class "Default")
      (node (ref "LINK") (pin "A") (pinfunction "A_A") (pintype "passive"))
      (node (ref "R72") (pin "2") (pinfunction "2_2") (pintype "passive"))
    )
    (net (code "131") (name "Net-(LINK-PadB)") (class "Default")
      (node (ref "LINK") (pin "B") (pinfunction "B_B") (pintype "passive"))
      (node (ref "T72") (pin "C") (pinfunction "C_C") (pintype "passive"))
    )
    (net (code "132") (name "Net-(MA0-PadA)") (class "Default")
      (node (ref "MA0") (pin "A") (pinfunction "A_A") (pintype "passive"))
      (node (ref "R19") (pin "2") (pinfunction "2_2") (pintype "passive"))
    )
    (net (code "133") (name "Net-(MA0-PadB)") (class "Default")
      (node (ref "MA0") (pin "B") (pinfunction "B_B") (pintype "passive"))
      (node (ref "T19") (pin "C") (pinfunction "C_C") (pintype "passive"))
    )
    (net (code "134") (name "Net-(MA1-PadA)") (class "Default")
      (node (ref "MA1") (pin "A") (pinfunction "A_A") (pintype "passive"))
      (node (ref "R20") (pin "2") (pinfunction "2_2") (pintype "passive"))
    )
    (net (code "135") (name "Net-(MA1-PadB)") (class "Default")
      (node (ref "MA1") (pin "B") (pinfunction "B_B") (pintype "passive"))
      (node (ref "T20") (pin "C") (pinfunction "C_C") (pintype "passive"))
    )
    (net (code "136") (name "Net-(MA2-PadA)") (class "Default")
      (node (ref "MA2") (pin "A") (pinfunction "A_A") (pintype "passive"))
      (node (ref "R21") (pin "2") (pinfunction "2_2") (pintype "passive"))
    )
    (net (code "137") (name "Net-(MA2-PadB)") (class "Default")
      (node (ref "MA2") (pin "B") (pinfunction "B_B") (pintype "passive"))
      (node (ref "T21") (pin "C") (pinfunction "C_C") (pintype "passive"))
    )
    (net (code "138") (name "Net-(MA3-PadA)") (class "Default")
      (node (ref "MA3") (pin "A") (pinfunction "A_A") (pintype "passive"))
      (node (ref "R22") (pin "2") (pinfunction "2_2") (pintype "passive"))
    )
    (net (code "139") (name "Net-(MA3-PadB)") (class "Default")
      (node (ref "MA3") (pin "B") (pinfunction "B_B") (pintype "passive"))
      (node (ref "T22") (pin "C") (pinfunction "C_C") (pintype "passive"))
    )
    (net (code "140") (name "Net-(MA4-PadA)") (class "Default")
      (node (ref "MA4") (pin "A") (pinfunction "A_A") (pintype "passive"))
      (node (ref "R23") (pin "2") (pinfunction "2_2") (pintype "passive"))
    )
    (net (code "141") (name "Net-(MA4-PadB)") (class "Default")
      (node (ref "MA4") (pin "B") (pinfunction "B_B") (pintype "passive"))
      (node (ref "T23") (pin "C") (pinfunction "C_C") (pintype "passive"))
    )
    (net (code "142") (name "Net-(MA5-PadA)") (class "Default")
      (node (ref "MA5") (pin "A") (pinfunction "A_A") (pintype "passive"))
      (node (ref "R24") (pin "2") (pinfunction "2_2") (pintype "passive"))
    )
    (net (code "143") (name "Net-(MA5-PadB)") (class "Default")
      (node (ref "MA5") (pin "B") (pinfunction "B_B") (pintype "passive"))
      (node (ref "T24") (pin "C") (pinfunction "C_C") (pintype "passive"))
    )
    (net (code "144") (name "Net-(MA6-PadA)") (class "Default")
      (node (ref "MA6") (pin "A") (pinfunction "A_A") (pintype "passive"))
      (node (ref "R25") (pin "2") (pinfunction "2_2") (pintype "passive"))
    )
    (net (code "145") (name "Net-(MA6-PadB)") (class "Default")
      (node (ref "MA6") (pin "B") (pinfunction "B_B") (pintype "passive"))
      (node (ref "T25") (pin "C") (pinfunction "C_C") (pintype "passive"))
    )
    (net (code "146") (name "Net-(MA7-PadA)") (class "Default")
      (node (ref "MA7") (pin "A") (pinfunction "A_A") (pintype "passive"))
      (node (ref "R26") (pin "2") (pinfunction "2_2") (pintype "passive"))
    )
    (net (code "147") (name "Net-(MA7-PadB)") (class "Default")
      (node (ref "MA7") (pin "B") (pinfunction "B_B") (pintype "passive"))
      (node (ref "T26") (pin "C") (pinfunction "C_C") (pintype "passive"))
    )
    (net (code "148") (name "Net-(MA8-PadA)") (class "Default")
      (node (ref "MA8") (pin "A") (pinfunction "A_A") (pintype "passive"))
      (node (ref "R27") (pin "2") (pinfunction "2_2") (pintype "passive"))
    )
    (net (code "149") (name "Net-(MA8-PadB)") (class "Default")
      (node (ref "MA8") (pin "B") (pinfunction "B_B") (pintype "passive"))
      (node (ref "T27") (pin "C") (pinfunction "C_C") (pintype "passive"))
    )
    (net (code "150") (name "Net-(MA9-PadA)") (class "Default")
      (node (ref "MA9") (pin "A") (pinfunction "A_A") (pintype "passive"))
      (node (ref "R28") (pin "2") (pinfunction "2_2") (pintype "passive"))
    )
    (net (code "151") (name "Net-(MA9-PadB)") (class "Default")
      (node (ref "MA9") (pin "B") (pinfunction "B_B") (pintype "passive"))
      (node (ref "T28") (pin "C") (pinfunction "C_C") (pintype "passive"))
    )
    (net (code "152") (name "Net-(MA10-PadA)") (class "Default")
      (node (ref "MA10") (pin "A") (pinfunction "A_A") (pintype "passive"))
      (node (ref "R29") (pin "2") (pinfunction "2_2") (pintype "passive"))
    )
    (net (code "153") (name "Net-(MA10-PadB)") (class "Default")
      (node (ref "MA10") (pin "B") (pinfunction "B_B") (pintype "passive"))
      (node (ref "T29") (pin "C") (pinfunction "C_C") (pintype "passive"))
    )
    (net (code "154") (name "Net-(MA11-PadA)") (class "Default")
      (node (ref "MA11") (pin "A") (pinfunction "A_A") (pintype "passive"))
      (node (ref "R30") (pin "2") (pinfunction "2_2") (pintype "passive"))
    )
    (net (code "155") (name "Net-(MA11-PadB)") (class "Default")
      (node (ref "MA11") (pin "B") (pinfunction "B_B") (pintype "passive"))
      (node (ref "T30") (pin "C") (pinfunction "C_C") (pintype "passive"))
    )
    (net (code "156") (name "Net-(MB0-PadA)") (class "Default")
      (node (ref "MB0") (pin "A") (pinfunction "A_A") (pintype "passive"))
      (node (ref "R31") (pin "2") (pinfunction "2_2") (pintype "passive"))
    )
    (net (code "157") (name "Net-(MB0-PadB)") (class "Default")
      (node (ref "MB0") (pin "B") (pinfunction "B_B") (pintype "passive"))
      (node (ref "T31") (pin "C") (pinfunction "C_C") (pintype "passive"))
    )
    (net (code "158") (name "Net-(MB1-PadA)") (class "Default")
      (node (ref "MB1") (pin "A") (pinfunction "A_A") (pintype "passive"))
      (node (ref "R32") (pin "2") (pinfunction "2_2") (pintype "passive"))
    )
    (net (code "159") (name "Net-(MB1-PadB)") (class "Default")
      (node (ref "MB1") (pin "B") (pinfunction "B_B") (pintype "passive"))
      (node (ref "T32") (pin "C") (pinfunction "C_C") (pintype "passive"))
    )
    (net (code "160") (name "Net-(MB2-PadA)") (class "Default")
      (node (ref "MB2") (pin "A") (pinfunction "A_A") (pintype "passive"))
      (node (ref "R33") (pin "2") (pinfunction "2_2") (pintype "passive"))
    )
    (net (code "161") (name "Net-(MB2-PadB)") (class "Default")
      (node (ref "MB2") (pin "B") (pinfunction "B_B") (pintype "passive"))
      (node (ref "T33") (pin "C") (pinfunction "C_C") (pintype "passive"))
    )
    (net (code "162") (name "Net-(MB3-PadA)") (class "Default")
      (node (ref "MB3") (pin "A") (pinfunction "A_A") (pintype "passive"))
      (node (ref "R34") (pin "2") (pinfunction "2_2") (pintype "passive"))
    )
    (net (code "163") (name "Net-(MB3-PadB)") (class "Default")
      (node (ref "MB3") (pin "B") (pinfunction "B_B") (pintype "passive"))
      (node (ref "T34") (pin "C") (pinfunction "C_C") (pintype "passive"))
    )
    (net (code "164") (name "Net-(MB4-PadA)") (class "Default")
      (node (ref "MB4") (pin "A") (pinfunction "A_A") (pintype "passive"))
      (node (ref "R35") (pin "2") (pinfunction "2_2") (pintype "passive"))
    )
    (net (code "165") (name "Net-(MB4-PadB)") (class "Default")
      (node (ref "MB4") (pin "B") (pinfunction "B_B") (pintype "passive"))
      (node (ref "T35") (pin "C") (pinfunction "C_C") (pintype "passive"))
    )
    (net (code "166") (name "Net-(MB5-PadA)") (class "Default")
      (node (ref "MB5") (pin "A") (pinfunction "A_A") (pintype "passive"))
      (node (ref "R36") (pin "2") (pinfunction "2_2") (pintype "passive"))
    )
    (net (code "167") (name "Net-(MB5-PadB)") (class "Default")
      (node (ref "MB5") (pin "B") (pinfunction "B_B") (pintype "passive"))
      (node (ref "T36") (pin "C") (pinfunction "C_C") (pintype "passive"))
    )
    (net (code "168") (name "Net-(MB6-PadA)") (class "Default")
      (node (ref "MB6") (pin "A") (pinfunction "A_A") (pintype "passive"))
      (node (ref "R37") (pin "2") (pinfunction "2_2") (pintype "passive"))
    )
    (net (code "169") (name "Net-(MB6-PadB)") (class "Default")
      (node (ref "MB6") (pin "B") (pinfunction "B_B") (pintype "passive"))
      (node (ref "T37") (pin "C") (pinfunction "C_C") (pintype "passive"))
    )
    (net (code "170") (name "Net-(MB7-PadA)") (class "Default")
      (node (ref "MB7") (pin "A") (pinfunction "A_A") (pintype "passive"))
      (node (ref "R38") (pin "2") (pinfunction "2_2") (pintype "passive"))
    )
    (net (code "171") (name "Net-(MB7-PadB)") (class "Default")
      (node (ref "MB7") (pin "B") (pinfunction "B_B") (pintype "passive"))
      (node (ref "T38") (pin "C") (pinfunction "C_C") (pintype "passive"))
    )
    (net (code "172") (name "Net-(MB8-PadA)") (class "Default")
      (node (ref "MB8") (pin "A") (pinfunction "A_A") (pintype "passive"))
      (node (ref "R39") (pin "2") (pinfunction "2_2") (pintype "passive"))
    )
    (net (code "173") (name "Net-(MB8-PadB)") (class "Default")
      (node (ref "MB8") (pin "B") (pinfunction "B_B") (pintype "passive"))
      (node (ref "T39") (pin "C") (pinfunction "C_C") (pintype "passive"))
    )
    (net (code "174") (name "Net-(MB9-PadA)") (class "Default")
      (node (ref "MB9") (pin "A") (pinfunction "A_A") (pintype "passive"))
      (node (ref "R40") (pin "2") (pinfunction "2_2") (pintype "passive"))
    )
    (net (code "175") (name "Net-(MB9-PadB)") (class "Default")
      (node (ref "MB9") (pin "B") (pinfunction "B_B") (pintype "passive"))
      (node (ref "T40") (pin "C") (pinfunction "C_C") (pintype "passive"))
    )
    (net (code "176") (name "Net-(MB10-PadA)") (class "Default")
      (node (ref "MB10") (pin "A") (pinfunction "A_A") (pintype "passive"))
      (node (ref "R41") (pin "2") (pinfunction "2_2") (pintype "passive"))
    )
    (net (code "177") (name "Net-(MB10-PadB)") (class "Default")
      (node (ref "MB10") (pin "B") (pinfunction "B_B") (pintype "passive"))
      (node (ref "T41") (pin "C") (pinfunction "C_C") (pintype "passive"))
    )
    (net (code "178") (name "Net-(MB11-PadA)") (class "Default")
      (node (ref "MB11") (pin "A") (pinfunction "A_A") (pintype "passive"))
      (node (ref "R42") (pin "2") (pinfunction "2_2") (pintype "passive"))
    )
    (net (code "179") (name "Net-(MB11-PadB)") (class "Default")
      (node (ref "MB11") (pin "B") (pinfunction "B_B") (pintype "passive"))
      (node (ref "T42") (pin "C") (pinfunction "C_C") (pintype "passive"))
    )
    (net (code "180") (name "Net-(MQ0-PadA)") (class "Default")
      (node (ref "MQ0") (pin "A") (pinfunction "A_A") (pintype "passive"))
      (node (ref "R55") (pin "2") (pinfunction "2_2") (pintype "passive"))
    )
    (net (code "181") (name "Net-(MQ0-PadB)") (class "Default")
      (node (ref "MQ0") (pin "B") (pinfunction "B_B") (pintype "passive"))
      (node (ref "T55") (pin "C") (pinfunction "C_C") (pintype "passive"))
    )
    (net (code "182") (name "Net-(MQ1-PadA)") (class "Default")
      (node (ref "MQ1") (pin "A") (pinfunction "A_A") (pintype "passive"))
      (node (ref "R56") (pin "2") (pinfunction "2_2") (pintype "passive"))
    )
    (net (code "183") (name "Net-(MQ1-PadB)") (class "Default")
      (node (ref "MQ1") (pin "B") (pinfunction "B_B") (pintype "passive"))
      (node (ref "T56") (pin "C") (pinfunction "C_C") (pintype "passive"))
    )
    (net (code "184") (name "Net-(MQ2-PadA)") (class "Default")
      (node (ref "MQ2") (pin "A") (pinfunction "A_A") (pintype "passive"))
      (node (ref "R57") (pin "2") (pinfunction "2_2") (pintype "passive"))
    )
    (net (code "185") (name "Net-(MQ2-PadB)") (class "Default")
      (node (ref "MQ2") (pin "B") (pinfunction "B_B") (pintype "passive"))
      (node (ref "T57") (pin "C") (pinfunction "C_C") (pintype "passive"))
    )
    (net (code "186") (name "Net-(MQ3-PadA)") (class "Default")
      (node (ref "MQ3") (pin "A") (pinfunction "A_A") (pintype "passive"))
      (node (ref "R58") (pin "2") (pinfunction "2_2") (pintype "passive"))
    )
    (net (code "187") (name "Net-(MQ3-PadB)") (class "Default")
      (node (ref "MQ3") (pin "B") (pinfunction "B_B") (pintype "passive"))
      (node (ref "T58") (pin "C") (pinfunction "C_C") (pintype "passive"))
    )
    (net (code "188") (name "Net-(MQ4-PadA)") (class "Default")
      (node (ref "MQ4") (pin "A") (pinfunction "A_A") (pintype "passive"))
      (node (ref "R59") (pin "2") (pinfunction "2_2") (pintype "passive"))
    )
    (net (code "189") (name "Net-(MQ4-PadB)") (class "Default")
      (node (ref "MQ4") (pin "B") (pinfunction "B_B") (pintype "passive"))
      (node (ref "T59") (pin "C") (pinfunction "C_C") (pintype "passive"))
    )
    (net (code "190") (name "Net-(MQ5-PadA)") (class "Default")
      (node (ref "MQ5") (pin "A") (pinfunction "A_A") (pintype "passive"))
      (node (ref "R60") (pin "2") (pinfunction "2_2") (pintype "passive"))
    )
    (net (code "191") (name "Net-(MQ5-PadB)") (class "Default")
      (node (ref "MQ5") (pin "B") (pinfunction "B_B") (pintype "passive"))
      (node (ref "T60") (pin "C") (pinfunction "C_C") (pintype "passive"))
    )
    (net (code "192") (name "Net-(MQ6-PadA)") (class "Default")
      (node (ref "MQ6") (pin "A") (pinfunction "A_A") (pintype "passive"))
      (node (ref "R61") (pin "2") (pinfunction "2_2") (pintype "passive"))
    )
    (net (code "193") (name "Net-(MQ6-PadB)") (class "Default")
      (node (ref "MQ6") (pin "B") (pinfunction "B_B") (pintype "passive"))
      (node (ref "T61") (pin "C") (pinfunction "C_C") (pintype "passive"))
    )
    (net (code "194") (name "Net-(MQ7-PadA)") (class "Default")
      (node (ref "MQ7") (pin "A") (pinfunction "A_A") (pintype "passive"))
      (node (ref "R62") (pin "2") (pinfunction "2_2") (pintype "passive"))
    )
    (net (code "195") (name "Net-(MQ7-PadB)") (class "Default")
      (node (ref "MQ7") (pin "B") (pinfunction "B_B") (pintype "passive"))
      (node (ref "T62") (pin "C") (pinfunction "C_C") (pintype "passive"))
    )
    (net (code "196") (name "Net-(MQ8-PadA)") (class "Default")
      (node (ref "MQ8") (pin "A") (pinfunction "A_A") (pintype "passive"))
      (node (ref "R63") (pin "2") (pinfunction "2_2") (pintype "passive"))
    )
    (net (code "197") (name "Net-(MQ8-PadB)") (class "Default")
      (node (ref "MQ8") (pin "B") (pinfunction "B_B") (pintype "passive"))
      (node (ref "T63") (pin "C") (pinfunction "C_C") (pintype "passive"))
    )
    (net (code "198") (name "Net-(MQ9-PadA)") (class "Default")
      (node (ref "MQ9") (pin "A") (pinfunction "A_A") (pintype "passive"))
      (node (ref "R64") (pin "2") (pinfunction "2_2") (pintype "passive"))
    )
    (net (code "199") (name "Net-(MQ9-PadB)") (class "Default")
      (node (ref "MQ9") (pin "B") (pinfunction "B_B") (pintype "passive"))
      (node (ref "T64") (pin "C") (pinfunction "C_C") (pintype "passive"))
    )
    (net (code "200") (name "Net-(MQ10-PadA)") (class "Default")
      (node (ref "MQ10") (pin "A") (pinfunction "A_A") (pintype "passive"))
      (node (ref "R65") (pin "2") (pinfunction "2_2") (pintype "passive"))
    )
    (net (code "201") (name "Net-(MQ10-PadB)") (class "Default")
      (node (ref "MQ10") (pin "B") (pinfunction "B_B") (pintype "passive"))
      (node (ref "T65") (pin "C") (pinfunction "C_C") (pintype "passive"))
    )
    (net (code "202") (name "Net-(MQ11-PadA)") (class "Default")
      (node (ref "MQ11") (pin "A") (pinfunction "A_A") (pintype "passive"))
      (node (ref "R66") (pin "2") (pinfunction "2_2") (pintype "passive"))
    )
    (net (code "203") (name "Net-(MQ11-PadB)") (class "Default")
      (node (ref "MQ11") (pin "B") (pinfunction "B_B") (pintype "passive"))
      (node (ref "T66") (pin "C") (pinfunction "C_C") (pintype "passive"))
    )
    (net (code "204") (name "Net-(OPR-PadA)") (class "Default")
      (node (ref "OPR") (pin "A") (pinfunction "A_A") (pintype "passive"))
      (node (ref "R89") (pin "2") (pinfunction "2_2") (pintype "passive"))
    )
    (net (code "205") (name "Net-(OPR-PadB)") (class "Default")
      (node (ref "OPR") (pin "B") (pinfunction "B_B") (pintype "passive"))
      (node (ref "T89") (pin "C") (pinfunction "C_C") (pintype "passive"))
    )
    (net (code "206") (name "Net-(PAUSE-PadA)") (class "Default")
      (node (ref "PAUSE") (pin "A") (pinfunction "A_A") (pintype "passive"))
      (node (ref "R74") (pin "2") (pinfunction "2_2") (pintype "passive"))
    )
    (net (code "207") (name "Net-(PAUSE-PadB)") (class "Default")
      (node (ref "PAUSE") (pin "B") (pinfunction "B_B") (pintype "passive"))
      (node (ref "T74") (pin "C") (pinfunction "C_C") (pintype "passive"))
    )
    (net (code "208") (name "Net-(PC0-PadA)") (class "Default")
      (node (ref "PC0") (pin "A") (pinfunction "A_A") (pintype "passive"))
      (node (ref "R7") (pin "2") (pinfunction "2_2") (pintype "passive"))
    )
    (net (code "209") (name "Net-(PC0-PadB)") (class "Default")
      (node (ref "PC0") (pin "B") (pinfunction "B_B") (pintype "passive"))
      (node (ref "T7") (pin "C") (pinfunction "C_C") (pintype "passive"))
    )
    (net (code "210") (name "Net-(PC1-PadA)") (class "Default")
      (node (ref "PC1") (pin "A") (pinfunction "A_A") (pintype "passive"))
      (node (ref "R8") (pin "2") (pinfunction "2_2") (pintype "passive"))
    )
    (net (code "211") (name "Net-(PC1-PadB)") (class "Default")
      (node (ref "PC1") (pin "B") (pinfunction "B_B") (pintype "passive"))
      (node (ref "T8") (pin "C") (pinfunction "C_C") (pintype "passive"))
    )
    (net (code "212") (name "Net-(PC2-PadA)") (class "Default")
      (node (ref "PC2") (pin "A") (pinfunction "A_A") (pintype "passive"))
      (node (ref "R9") (pin "2") (pinfunction "2_2") (pintype "passive"))
    )
    (net (code "213") (name "Net-(PC2-PadB)") (class "Default")
      (node (ref "PC2") (pin "B") (pinfunction "B_B") (pintype "passive"))
      (node (ref "T9") (pin "C") (pinfunction "C_C") (pintype "passive"))
    )
    (net (code "214") (name "Net-(PC3-PadA)") (class "Default")
      (node (ref "PC3") (pin "A") (pinfunction "A_A") (pintype "passive"))
      (node (ref "R10") (pin "2") (pinfunction "2_2") (pintype "passive"))
    )
    (net (code "215") (name "Net-(PC3-PadB)") (class "Default")
      (node (ref "PC3") (pin "B") (pinfunction "B_B") (pintype "passive"))
      (node (ref "T10") (pin "C") (pinfunction "C_C") (pintype "passive"))
    )
    (net (code "216") (name "Net-(PC4-PadA)") (class "Default")
      (node (ref "PC4") (pin "A") (pinfunction "A_A") (pintype "passive"))
      (node (ref "R11") (pin "2") (pinfunction "2_2") (pintype "passive"))
    )
    (net (code "217") (name "Net-(PC4-PadB)") (class "Default")
      (node (ref "PC4") (pin "B") (pinfunction "B_B") (pintype "passive"))
      (node (ref "T11") (pin "C") (pinfunction "C_C") (pintype "passive"))
    )
    (net (code "218") (name "Net-(PC5-PadA)") (class "Default")
      (node (ref "PC5") (pin "A") (pinfunction "A_A") (pintype "passive"))
      (node (ref "R12") (pin "2") (pinfunction "2_2") (pintype "passive"))
    )
    (net (code "219") (name "Net-(PC5-PadB)") (class "Default")
      (node (ref "PC5") (pin "B") (pinfunction "B_B") (pintype "passive"))
      (node (ref "T12") (pin "C") (pinfunction "C_C") (pintype "passive"))
    )
    (net (code "220") (name "Net-(PC6-PadA)") (class "Default")
      (node (ref "PC6") (pin "A") (pinfunction "A_A") (pintype "passive"))
      (node (ref "R13") (pin "2") (pinfunction "2_2") (pintype "passive"))
    )
    (net (code "221") (name "Net-(PC6-PadB)") (class "Default")
      (node (ref "PC6") (pin "B") (pinfunction "B_B") (pintype "passive"))
      (node (ref "T13") (pin "C") (pinfunction "C_C") (pintype "passive"))
    )
    (net (code "222") (name "Net-(PC7-PadA)") (class "Default")
      (node (ref "PC7") (pin "A") (pinfunction "A_A") (pintype "passive"))
      (node (ref "R14") (pin "2") (pinfunction "2_2") (pintype "passive"))
    )
    (net (code "223") (name "Net-(PC7-PadB)") (class "Default")
      (node (ref "PC7") (pin "B") (pinfunction "B_B") (pintype "passive"))
      (node (ref "T14") (pin "C") (pinfunction "C_C") (pintype "passive"))
    )
    (net (code "224") (name "Net-(PC8-PadA)") (class "Default")
      (node (ref "PC8") (pin "A") (pinfunction "A_A") (pintype "passive"))
      (node (ref "R15") (pin "2") (pinfunction "2_2") (pintype "passive"))
    )
    (net (code "225") (name "Net-(PC8-PadB)") (class "Default")
      (node (ref "PC8") (pin "B") (pinfunction "B_B") (pintype "passive"))
      (node (ref "T15") (pin "C") (pinfunction "C_C") (pintype "passive"))
    )
    (net (code "226") (name "Net-(PC9-PadA)") (class "Default")
      (node (ref "PC9") (pin "A") (pinfunction "A_A") (pintype "passive"))
      (node (ref "R16") (pin "2") (pinfunction "2_2") (pintype "passive"))
    )
    (net (code "227") (name "Net-(PC9-PadB)") (class "Default")
      (node (ref "PC9") (pin "B") (pinfunction "B_B") (pintype "passive"))
      (node (ref "T16") (pin "C") (pinfunction "C_C") (pintype "passive"))
    )
    (net (code "228") (name "Net-(PC10-PadA)") (class "Default")
      (node (ref "PC10") (pin "A") (pinfunction "A_A") (pintype "passive"))
      (node (ref "R17") (pin "2") (pinfunction "2_2") (pintype "passive"))
    )
    (net (code "229") (name "Net-(PC10-PadB)") (class "Default")
      (node (ref "PC10") (pin "B") (pinfunction "B_B") (pintype "passive"))
      (node (ref "T17") (pin "C") (pinfunction "C_C") (pintype "passive"))
    )
    (net (code "230") (name "Net-(PC11-PadA)") (class "Default")
      (node (ref "PC11") (pin "A") (pinfunction "A_A") (pintype "passive"))
      (node (ref "R18") (pin "2") (pinfunction "2_2") (pintype "passive"))
    )
    (net (code "231") (name "Net-(PC11-PadB)") (class "Default")
      (node (ref "PC11") (pin "B") (pinfunction "B_B") (pintype "passive"))
      (node (ref "T18") (pin "C") (pinfunction "C_C") (pintype "passive"))
    )
    (net (code "232") (name "Net-(R67-Pad2)") (class "Default")
      (node (ref "R67") (pin "2") (pinfunction "2_2") (pintype "passive"))
      (node (ref "SC0") (pin "A") (pinfunction "A_A") (pintype "passive"))
    )
    (net (code "233") (name "Net-(R68-Pad2)") (class "Default")
      (node (ref "R68") (pin "2") (pinfunction "2_2") (pintype "passive"))
      (node (ref "SC1") (pin "A") (pinfunction "A_A") (pintype "passive"))
    )
    (net (code "234") (name "Net-(R69-Pad2)") (class "Default")
      (node (ref "R69") (pin "2") (pinfunction "2_2") (pintype "passive"))
      (node (ref "SC2") (pin "A") (pinfunction "A_A") (pintype "passive"))
    )
    (net (code "235") (name "Net-(R70-Pad2)") (class "Default")
      (node (ref "R70") (pin "2") (pinfunction "2_2") (pintype "passive"))
      (node (ref "SC3") (pin "A") (pinfunction "A_A") (pintype "passive"))
    )
    (net (code "236") (name "Net-(R71-Pad2)") (class "Default")
      (node (ref "R71") (pin "2") (pinfunction "2_2") (pintype "passive"))
      (node (ref "SC4") (pin "A") (pinfunction "A_A") (pintype "passive"))
    )
    (net (code "237") (name "Net-(R75-Pad2)") (class "Default")
      (node (ref "R75") (pin "2") (pinfunction "2_2") (pintype "passive"))
      (node (ref "RUN") (pin "A") (pinfunction "A_A") (pintype "passive"))
    )
    (net (code "238") (name "Net-(R79-Pad2)") (class "Default")
      (node (ref "R79") (pin "2") (pinfunction "2_2") (pintype "passive"))
      (node (ref "WORDCOUNT") (pin "A") (pinfunction "A_A") (pintype "passive"))
    )
    (net (code "239") (name "Net-(R83-Pad2)") (class "Default")
      (node (ref "R83") (pin "2") (pinfunction "2_2") (pintype "passive"))
      (node (ref "TAD") (pin "A") (pinfunction "A_A") (pintype "passive"))
    )
    (net (code "240") (name "Net-(RUN-PadB)") (class "Default")
      (node (ref "RUN") (pin "B") (pinfunction "B_B") (pintype "passive"))
      (node (ref "T75") (pin "C") (pinfunction "C_C") (pintype "passive"))
    )
    (net (code "241") (name "Net-(SC0-PadB)") (class "Default")
      (node (ref "SC0") (pin "B") (pinfunction "B_B") (pintype "passive"))
      (node (ref "T67") (pin "C") (pinfunction "C_C") (pintype "passive"))
    )
    (net (code "242") (name "Net-(SC1-PadB)") (class "Default")
      (node (ref "SC1") (pin "B") (pinfunction "B_B") (pintype "passive"))
      (node (ref "T68") (pin "C") (pinfunction "C_C") (pintype "passive"))
    )
    (net (code "243") (name "Net-(SC2-PadB)") (class "Default")
      (node (ref "SC2") (pin "B") (pinfunction "B_B") (pintype "passive"))
      (node (ref "T69") (pin "C") (pinfunction "C_C") (pintype "passive"))
    )
    (net (code "244") (name "Net-(SC3-PadB)") (class "Default")
      (node (ref "SC3") (pin "B") (pinfunction "B_B") (pintype "passive"))
      (node (ref "T70") (pin "C") (pinfunction "C_C") (pintype "passive"))
    )
    (net (code "245") (name "Net-(SC4-PadB)") (class "Default")
      (node (ref "SC4") (pin "B") (pinfunction "B_B") (pintype "passive"))
      (node (ref "T71") (pin "C") (pinfunction "C_C") (pintype "passive"))
    )
    (net (code "246") (name "Net-(T79-PadC)") (class "Default")
      (node (ref "T79") (pin "C") (pinfunction "C_C") (pintype "passive"))
      (node (ref "WORDCOUNT") (pin "B") (pinfunction "B_B") (pintype "passive"))
    )
    (net (code "247") (name "Net-(T83-PadC)") (class "Default")
      (node (ref "T83") (pin "C") (pinfunction "C_C") (pintype "passive"))
      (node (ref "TAD") (pin "B") (pinfunction "B_B") (pintype "passive"))
    )
    (net (code "248") (name "OPR") (class "Default")
      (node (ref "D40") (pin "16") (pinfunction "16_16") (pintype "passive"))
      (node (ref "F40BOT") (pin "11") (pinfunction "1_11") (pintype "passive"))
      (node (ref "T89") (pin "B") (pinfunction "B_B") (pintype "passive"))
    )
    (net (code "249") (name "PAUSE") (class "Default")
      (node (ref "D40") (pin "31") (pinfunction "31_31") (pintype "passive"))
      (node (ref "F40TOP") (pin "17") (pinfunction "1_17") (pintype "passive"))
      (node (ref "T74") (pin "B") (pinfunction "B_B") (pintype "passive"))
    )
    (net (code "250") (name "PC0") (class "Default")
      (node (ref "D40TOP") (pin "1") (pinfunction "1_1") (pintype "passive"))
      (node (ref "E40") (pin "1") (pinfunction "1_1") (pintype "passive"))
      (node (ref "T7") (pin "B") (pinfunction "B_B") (pintype "passive"))
    )
    (net (code "251") (name "PC1") (class "Default")
      (node (ref "D40BOT") (pin "5") (pinfunction "1_5") (pintype "passive"))
      (node (ref "E40") (pin "10") (pinfunction "10_10") (pintype "passive"))
      (node (ref "T8") (pin "B") (pinfunction "B_B") (pintype "passive"))
    )
    (net (code "252") (name "PC2") (class "Default")
      (node (ref "D40TOP") (pin "6") (pinfunction "1_6") (pintype "passive"))
      (node (ref "E40") (pin "11") (pinfunction "11_11") (pintype "passive"))
      (node (ref "T9") (pin "B") (pinfunction "B_B") (pintype "passive"))
    )
    (net (code "253") (name "PC3") (class "Default")
      (node (ref "D40BOT") (pin "14") (pinfunction "1_14") (pintype "passive"))
      (node (ref "E40") (pin "24") (pinfunction "24_24") (pintype "passive"))
      (node (ref "T10") (pin "B") (pinfunction "B_B") (pintype "passive"))
    )
    (net (code "254") (name "PC4") (class "Default")
      (node (ref "D40TOP") (pin "14") (pinfunction "1_14") (pintype "passive"))
      (node (ref "E40") (pin "25") (pinfunction "25_25") (pintype "passive"))
      (node (ref "T11") (pin "B") (pinfunction "B_B") (pintype "passive"))
    )
    (net (code "255") (name "PC5") (class "Default")
      (node (ref "D40BOT") (pin "19") (pinfunction "1_19") (pintype "passive"))
      (node (ref "E40") (pin "34") (pinfunction "34_34") (pintype "passive"))
      (node (ref "T12") (pin "B") (pinfunction "B_B") (pintype "passive"))
    )
    (net (code "256") (name "PC6") (class "Default")
      (node (ref "E40TOP") (pin "1") (pinfunction "1_1") (pintype "passive"))
      (node (ref "F40") (pin "1") (pinfunction "1_1") (pintype "passive"))
      (node (ref "T13") (pin "B") (pinfunction "B_B") (pintype "passive"))
    )
    (net (code "257") (name "PC7") (class "Default")
      (node (ref "E40BOT") (pin "5") (pinfunction "1_5") (pintype "passive"))
      (node (ref "F40") (pin "10") (pinfunction "10_10") (pintype "passive"))
      (node (ref "T14") (pin "B") (pinfunction "B_B") (pintype "passive"))
    )
    (net (code "258") (name "PC8") (class "Default")
      (node (ref "E40TOP") (pin "6") (pinfunction "1_6") (pintype "passive"))
      (node (ref "F40") (pin "11") (pinfunction "11_11") (pintype "passive"))
      (node (ref "T15") (pin "B") (pinfunction "B_B") (pintype "passive"))
    )
    (net (code "259") (name "PC9") (class "Default")
      (node (ref "E40BOT") (pin "14") (pinfunction "1_14") (pintype "passive"))
      (node (ref "F40") (pin "24") (pinfunction "24_24") (pintype "passive"))
      (node (ref "T16") (pin "B") (pinfunction "B_B") (pintype "passive"))
    )
    (net (code "260") (name "PC10") (class "Default")
      (node (ref "E40TOP") (pin "14") (pinfunction "1_14") (pintype "passive"))
      (node (ref "F40") (pin "25") (pinfunction "25_25") (pintype "passive"))
      (node (ref "T17") (pin "B") (pinfunction "B_B") (pintype "passive"))
    )
    (net (code "261") (name "PC11") (class "Default")
      (node (ref "E40BOT") (pin "19") (pinfunction "1_19") (pintype "passive"))
      (node (ref "F40") (pin "34") (pinfunction "34_34") (pintype "passive"))
      (node (ref "T18") (pin "B") (pinfunction "B_B") (pintype "passive"))
    )
    (net (code "262") (name "RUN") (class "Default")
      (node (ref "D40") (pin "33") (pinfunction "33_33") (pintype "passive"))
      (node (ref "F40TOP") (pin "18") (pinfunction "1_18") (pintype "passive"))
      (node (ref "T75") (pin "B") (pinfunction "B_B") (pintype "passive"))
    )
    (net (code "263") (name "SC0") (class "Default")
      (node (ref "C40") (pin "9") (pinfunction "9_9") (pintype "passive"))
      (node (ref "C40TOP") (pin "5") (pinfunction "1_5") (pintype "passive"))
      (node (ref "T67") (pin "B") (pinfunction "B_B") (pintype "passive"))
    )
    (net (code "264") (name "SC1") (class "Default")
      (node (ref "C40") (pin "2") (pinfunction "2_2") (pintype "passive"))
      (node (ref "C40BOT") (pin "1") (pinfunction "1_1") (pintype "passive"))
      (node (ref "T68") (pin "B") (pinfunction "B_B") (pintype "passive"))
    )
    (net (code "265") (name "SC2") (class "Default")
      (node (ref "C40") (pin "23") (pinfunction "23_23") (pintype "passive"))
      (node (ref "C40TOP") (pin "13") (pinfunction "1_13") (pintype "passive"))
      (node (ref "T69") (pin "B") (pinfunction "B_B") (pintype "passive"))
    )
    (net (code "266") (name "SC3") (class "Default")
      (node (ref "C40") (pin "12") (pinfunction "12_12") (pintype "passive"))
      (node (ref "C40BOT") (pin "6") (pinfunction "1_6") (pintype "passive"))
      (node (ref "T70") (pin "B") (pinfunction "B_B") (pintype "passive"))
    )
    (net (code "267") (name "SC4") (class "Default")
      (node (ref "C40") (pin "33") (pinfunction "33_33") (pintype "passive"))
      (node (ref "C40TOP") (pin "18") (pinfunction "1_18") (pintype "passive"))
      (node (ref "T71") (pin "B") (pinfunction "B_B") (pintype "passive"))
    )
    (net (code "268") (name "TAD") (class "Default")
      (node (ref "D40") (pin "4") (pinfunction "4_4") (pintype "passive"))
      (node (ref "F40BOT") (pin "2") (pinfunction "1_2") (pintype "passive"))
      (node (ref "T83") (pin "B") (pinfunction "B_B") (pintype "passive"))
    )
    (net (code "269") (name "WC") (class "Default")
      (node (ref "D40") (pin "30") (pinfunction "30_30") (pintype "passive"))
      (node (ref "F40BOT") (pin "17") (pinfunction "1_17") (pintype "passive"))
      (node (ref "T79") (pin "B") (pinfunction "B_B") (pintype "passive"))
    )
    (net (code "270") (name "unconnected-(C40-Pad3)") (class "Default")
      (node (ref "C40") (pin "3") (pinfunction "3_3") (pintype "passive"))
    )
    (net (code "271") (name "unconnected-(C40-Pad4)") (class "Default")
      (node (ref "C40") (pin "4") (pinfunction "4_4") (pintype "passive"))
    )
    (net (code "272") (name "unconnected-(C40-Pad5)") (class "Default")
      (node (ref "C40") (pin "5") (pinfunction "5_5") (pintype "passive"))
    )
    (net (code "273") (name "unconnected-(C40-Pad6)") (class "Default")
      (node (ref "C40") (pin "6") (pinfunction "6_6") (pintype "passive"))
    )
    (net (code "274") (name "unconnected-(C40-Pad7)") (class "Default")
      (node (ref "C40") (pin "7") (pinfunction "7_7") (pintype "passive"))
    )
    (net (code "275") (name "unconnected-(C40-Pad8)") (class "Default")
      (node (ref "C40") (pin "8") (pinfunction "8_8") (pintype "passive"))
    )
    (net (code "276") (name "unconnected-(C40-Pad13)") (class "Default")
      (node (ref "C40") (pin "13") (pinfunction "13_13") (pintype "passive"))
    )
    (net (code "277") (name "unconnected-(C40-Pad14)") (class "Default")
      (node (ref "C40") (pin "14") (pinfunction "14_14") (pintype "passive"))
    )
    (net (code "278") (name "unconnected-(C40-Pad15)") (class "Default")
      (node (ref "C40") (pin "15") (pinfunction "15_15") (pintype "passive"))
    )
    (net (code "279") (name "unconnected-(C40-Pad16)") (class "Default")
      (node (ref "C40") (pin "16") (pinfunction "16_16") (pintype "passive"))
    )
    (net (code "280") (name "unconnected-(C40-Pad21)") (class "Default")
      (node (ref "C40") (pin "21") (pinfunction "21_21") (pintype "passive"))
    )
    (net (code "281") (name "unconnected-(C40-Pad22)") (class "Default")
      (node (ref "C40") (pin "22") (pinfunction "22_22") (pintype "passive"))
    )
    (net (code "282") (name "unconnected-(C40-Pad26)") (class "Default")
      (node (ref "C40") (pin "26") (pinfunction "26_26") (pintype "passive"))
    )
    (net (code "283") (name "unconnected-(C40-Pad27)") (class "Default")
      (node (ref "C40") (pin "27") (pinfunction "27_27") (pintype "passive"))
    )
    (net (code "284") (name "unconnected-(C40-Pad29)") (class "Default")
      (node (ref "C40") (pin "29") (pinfunction "29_29") (pintype "passive"))
    )
    (net (code "285") (name "unconnected-(C40-Pad30)") (class "Default")
      (node (ref "C40") (pin "30") (pinfunction "30_30") (pintype "passive"))
    )
    (net (code "286") (name "unconnected-(C40-Pad31)") (class "Default")
      (node (ref "C40") (pin "31") (pinfunction "31_31") (pintype "passive"))
    )
    (net (code "287") (name "unconnected-(C40-Pad32)") (class "Default")
      (node (ref "C40") (pin "32") (pinfunction "32_32") (pintype "passive"))
    )
    (net (code "288") (name "unconnected-(D40-Pad1)") (class "Default")
      (node (ref "D40") (pin "1") (pinfunction "1_1") (pintype "passive"))
    )
    (net (code "289") (name "unconnected-(D40-Pad3)") (class "Default")
      (node (ref "D40") (pin "3") (pinfunction "3_3") (pintype "passive"))
    )
    (net (code "290") (name "unconnected-(D40-Pad5)") (class "Default")
      (node (ref "D40") (pin "5") (pinfunction "5_5") (pintype "passive"))
    )
    (net (code "291") (name "unconnected-(D40-Pad7)") (class "Default")
      (node (ref "D40") (pin "7") (pinfunction "7_7") (pintype "passive"))
    )
    (net (code "292") (name "unconnected-(D40-Pad9)") (class "Default")
      (node (ref "D40") (pin "9") (pinfunction "9_9") (pintype "passive"))
    )
    (net (code "293") (name "unconnected-(D40-Pad11)") (class "Default")
      (node (ref "D40") (pin "11") (pinfunction "11_11") (pintype "passive"))
    )
    (net (code "294") (name "unconnected-(D40-Pad13)") (class "Default")
      (node (ref "D40") (pin "13") (pinfunction "13_13") (pintype "passive"))
    )
    (net (code "295") (name "unconnected-(D40-Pad14)") (class "Default")
      (node (ref "D40") (pin "14") (pinfunction "14_14") (pintype "passive"))
    )
    (net (code "296") (name "unconnected-(D40-Pad15)") (class "Default")
      (node (ref "D40") (pin "15") (pinfunction "15_15") (pintype "passive"))
    )
    (net (code "297") (name "unconnected-(D40-Pad21)") (class "Default")
      (node (ref "D40") (pin "21") (pinfunction "21_21") (pintype "passive"))
    )
    (net (code "298") (name "unconnected-(D40-Pad25)") (class "Default")
      (node (ref "D40") (pin "25") (pinfunction "25_25") (pintype "passive"))
    )
    (net (code "299") (name "unconnected-(D40-Pad27)") (class "Default")
      (node (ref "D40") (pin "27") (pinfunction "27_27") (pintype "passive"))
    )
    (net (code "300") (name "unconnected-(D40-Pad29)") (class "Default")
      (node (ref "D40") (pin "29") (pinfunction "29_29") (pintype "passive"))
    )
  )
)
